# senseBox-MCU_v15.net
KiCad netlist of a schematic drawn in EAGLE
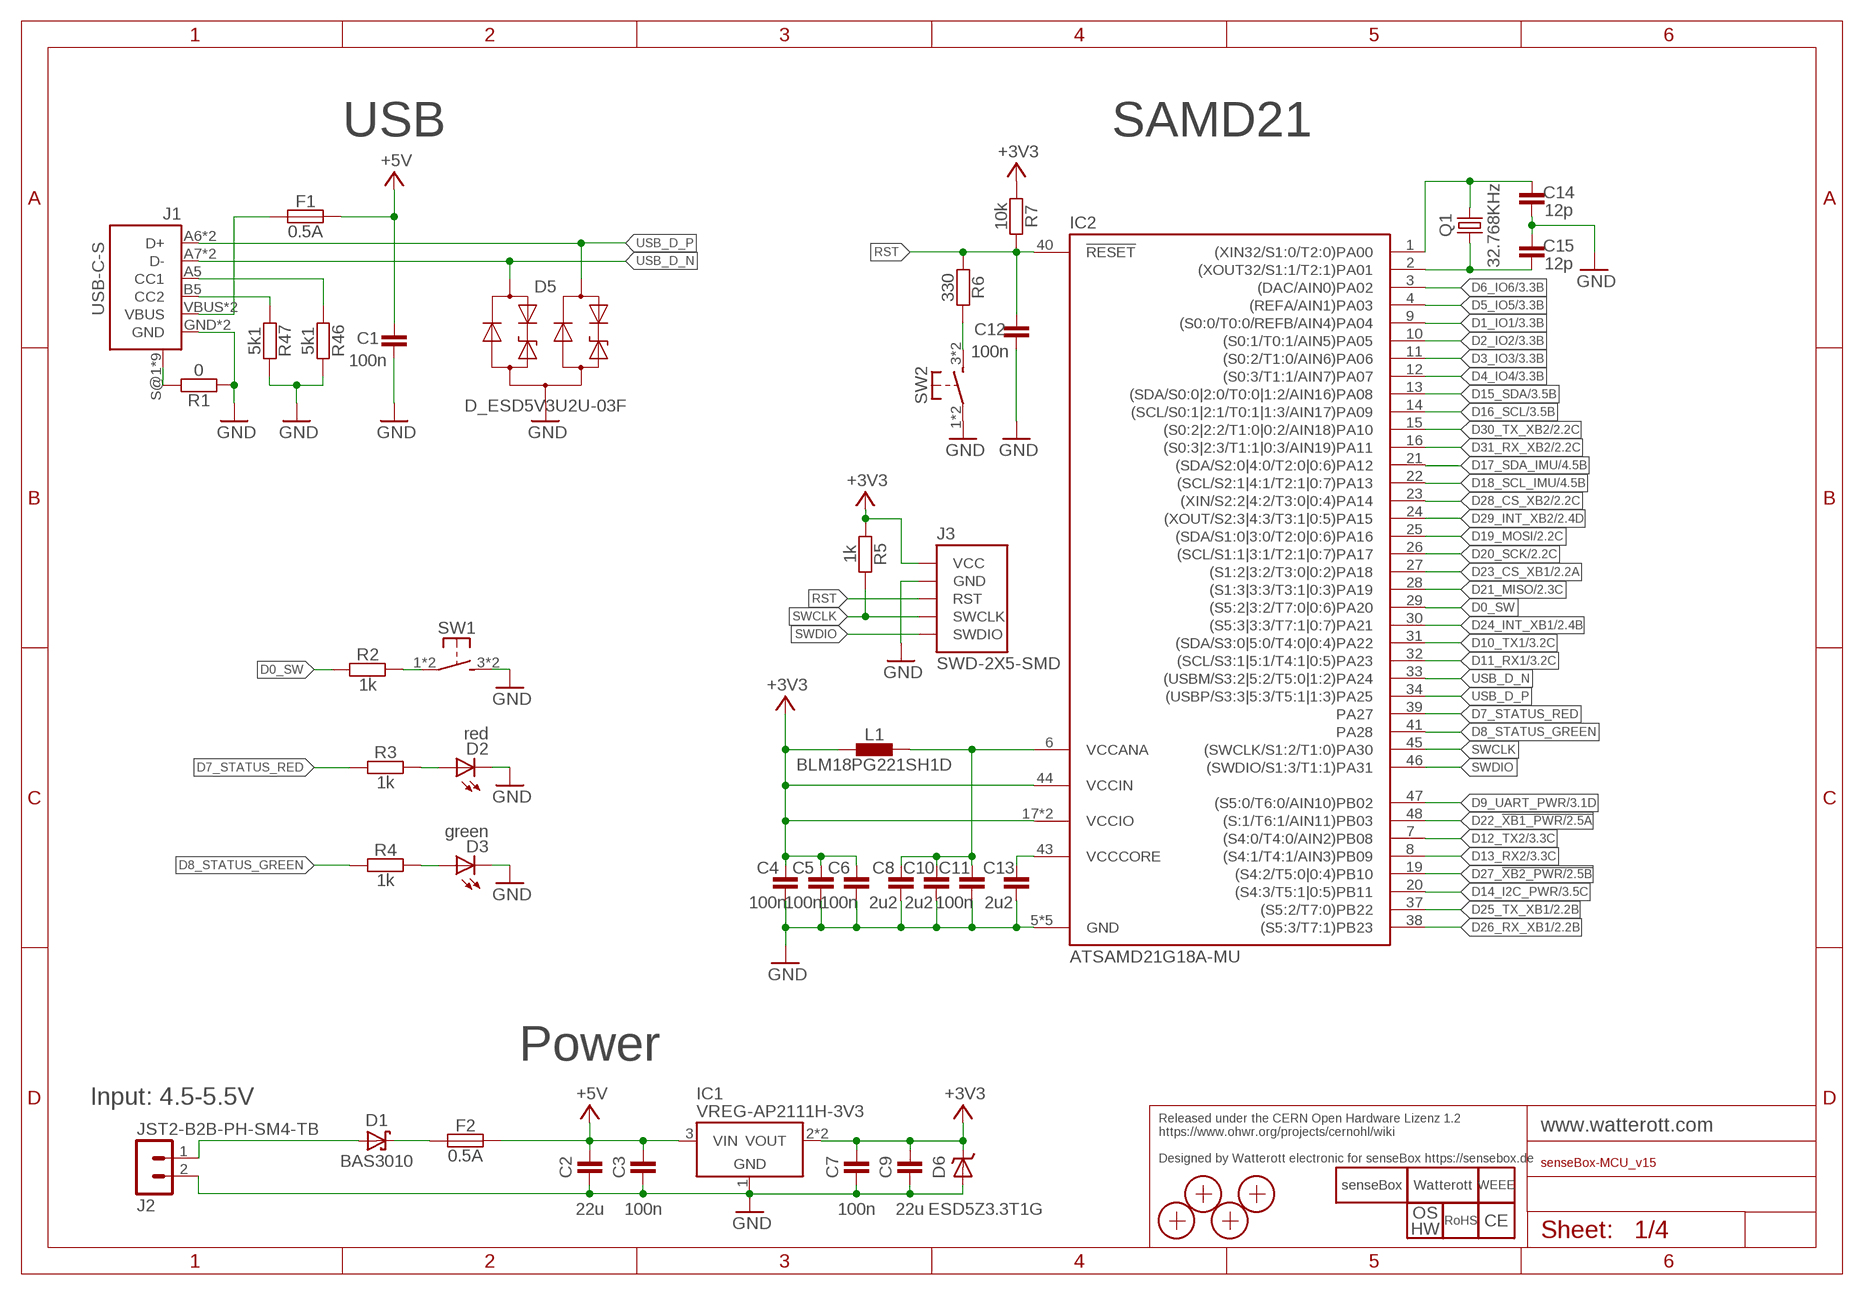
[diagram p0: schematic, sheet 1]
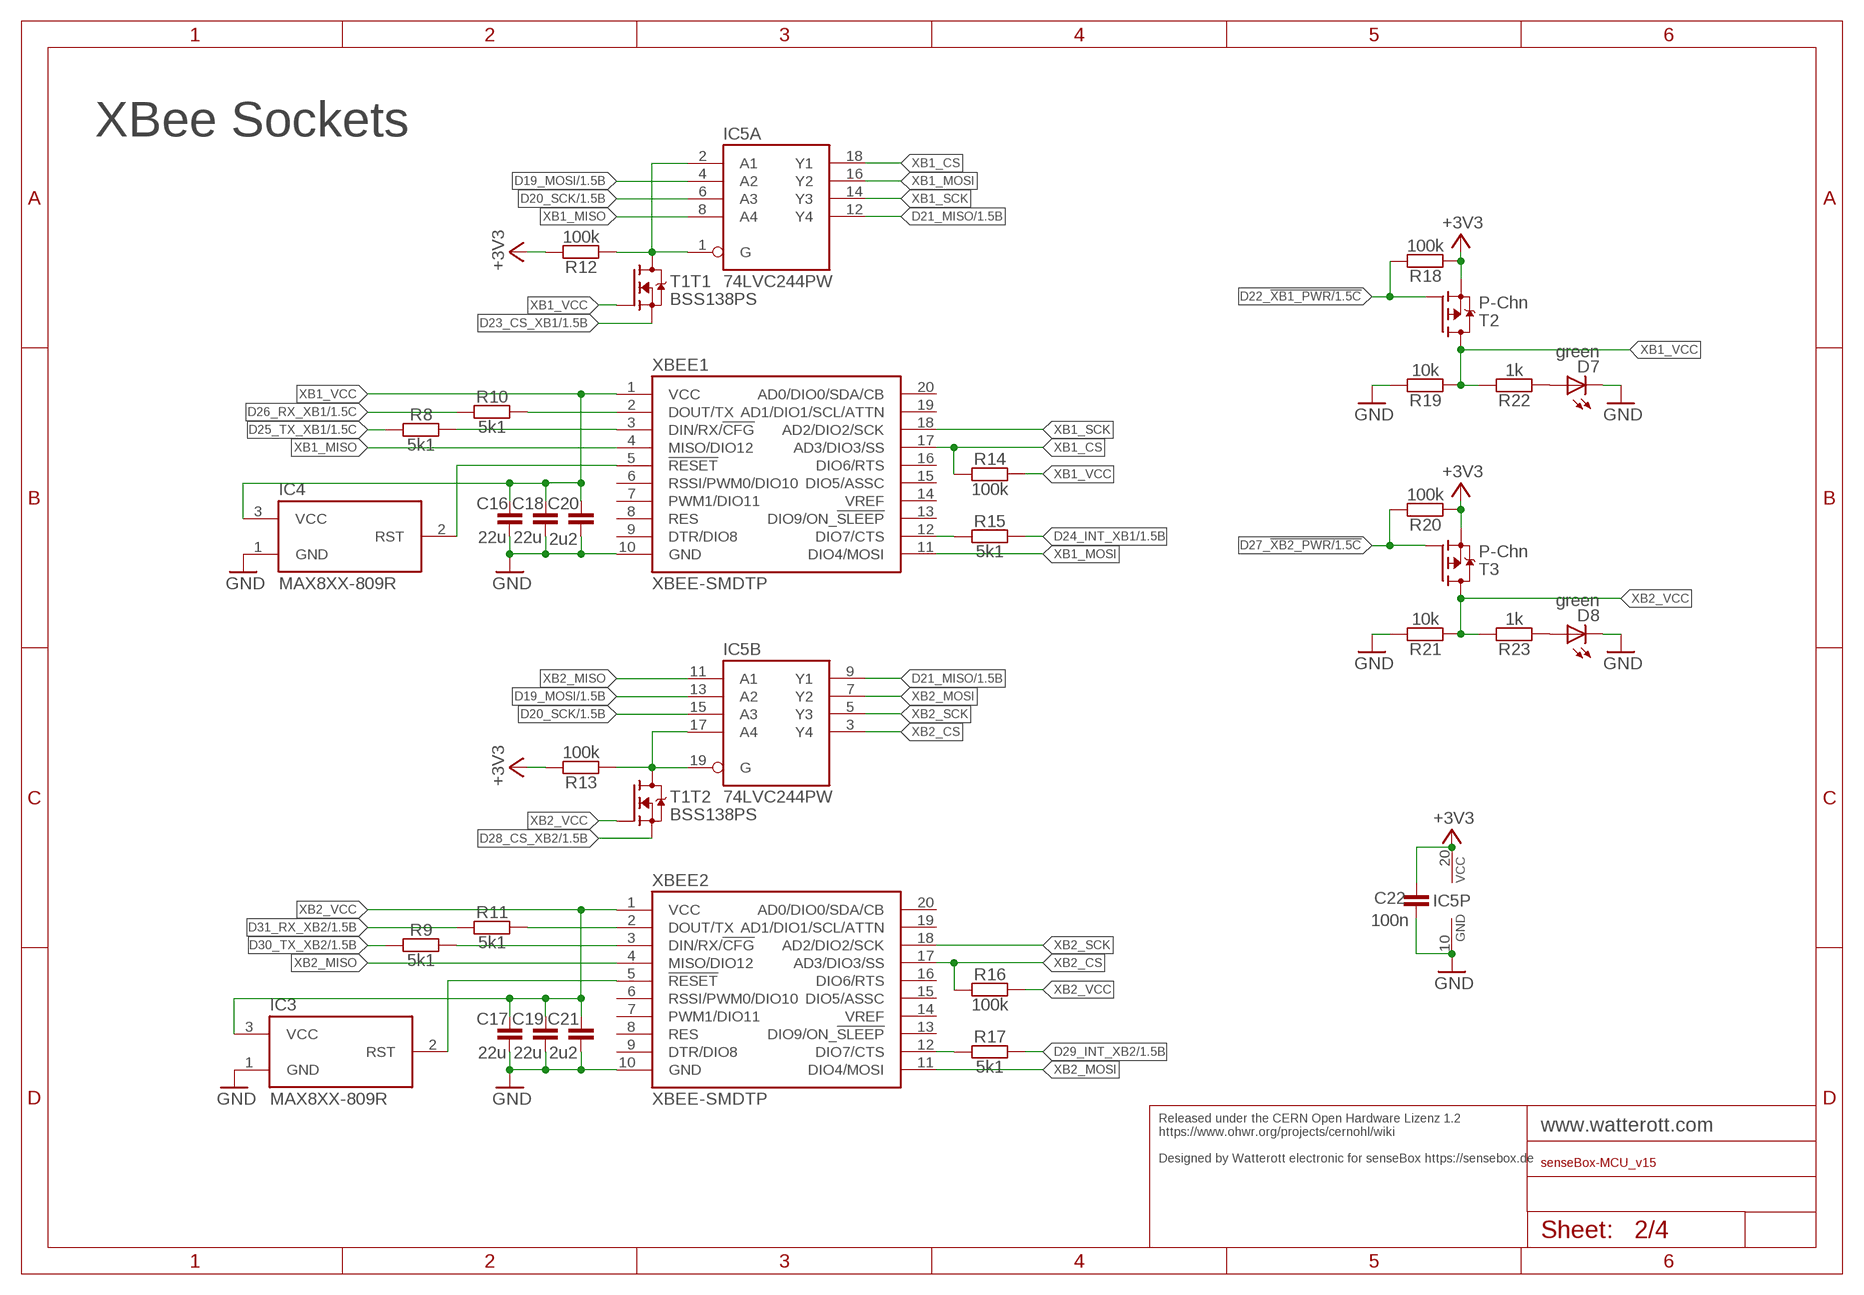
[diagram p1: schematic, sheet 2]
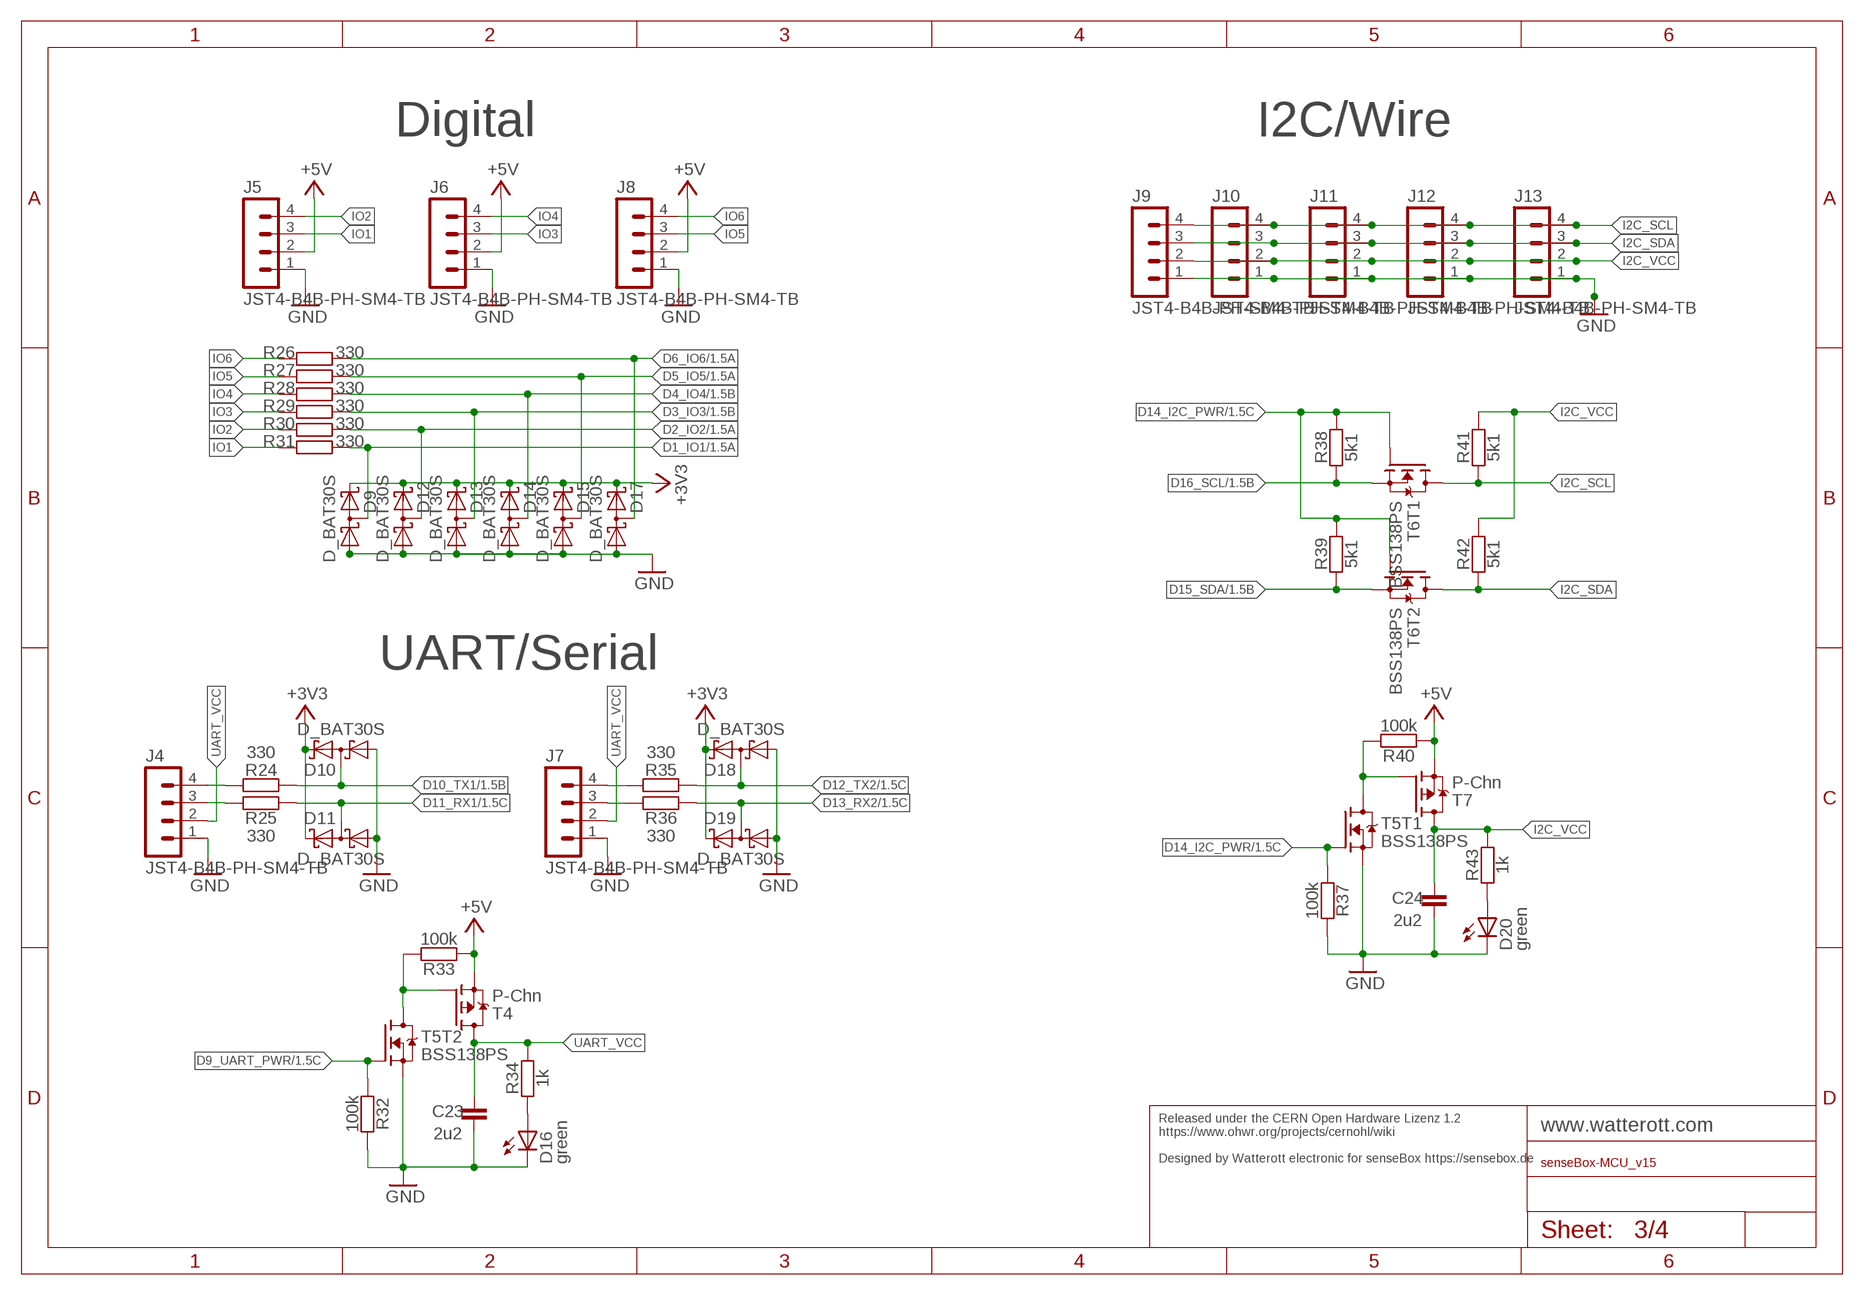
[diagram p2: schematic, sheet 3]
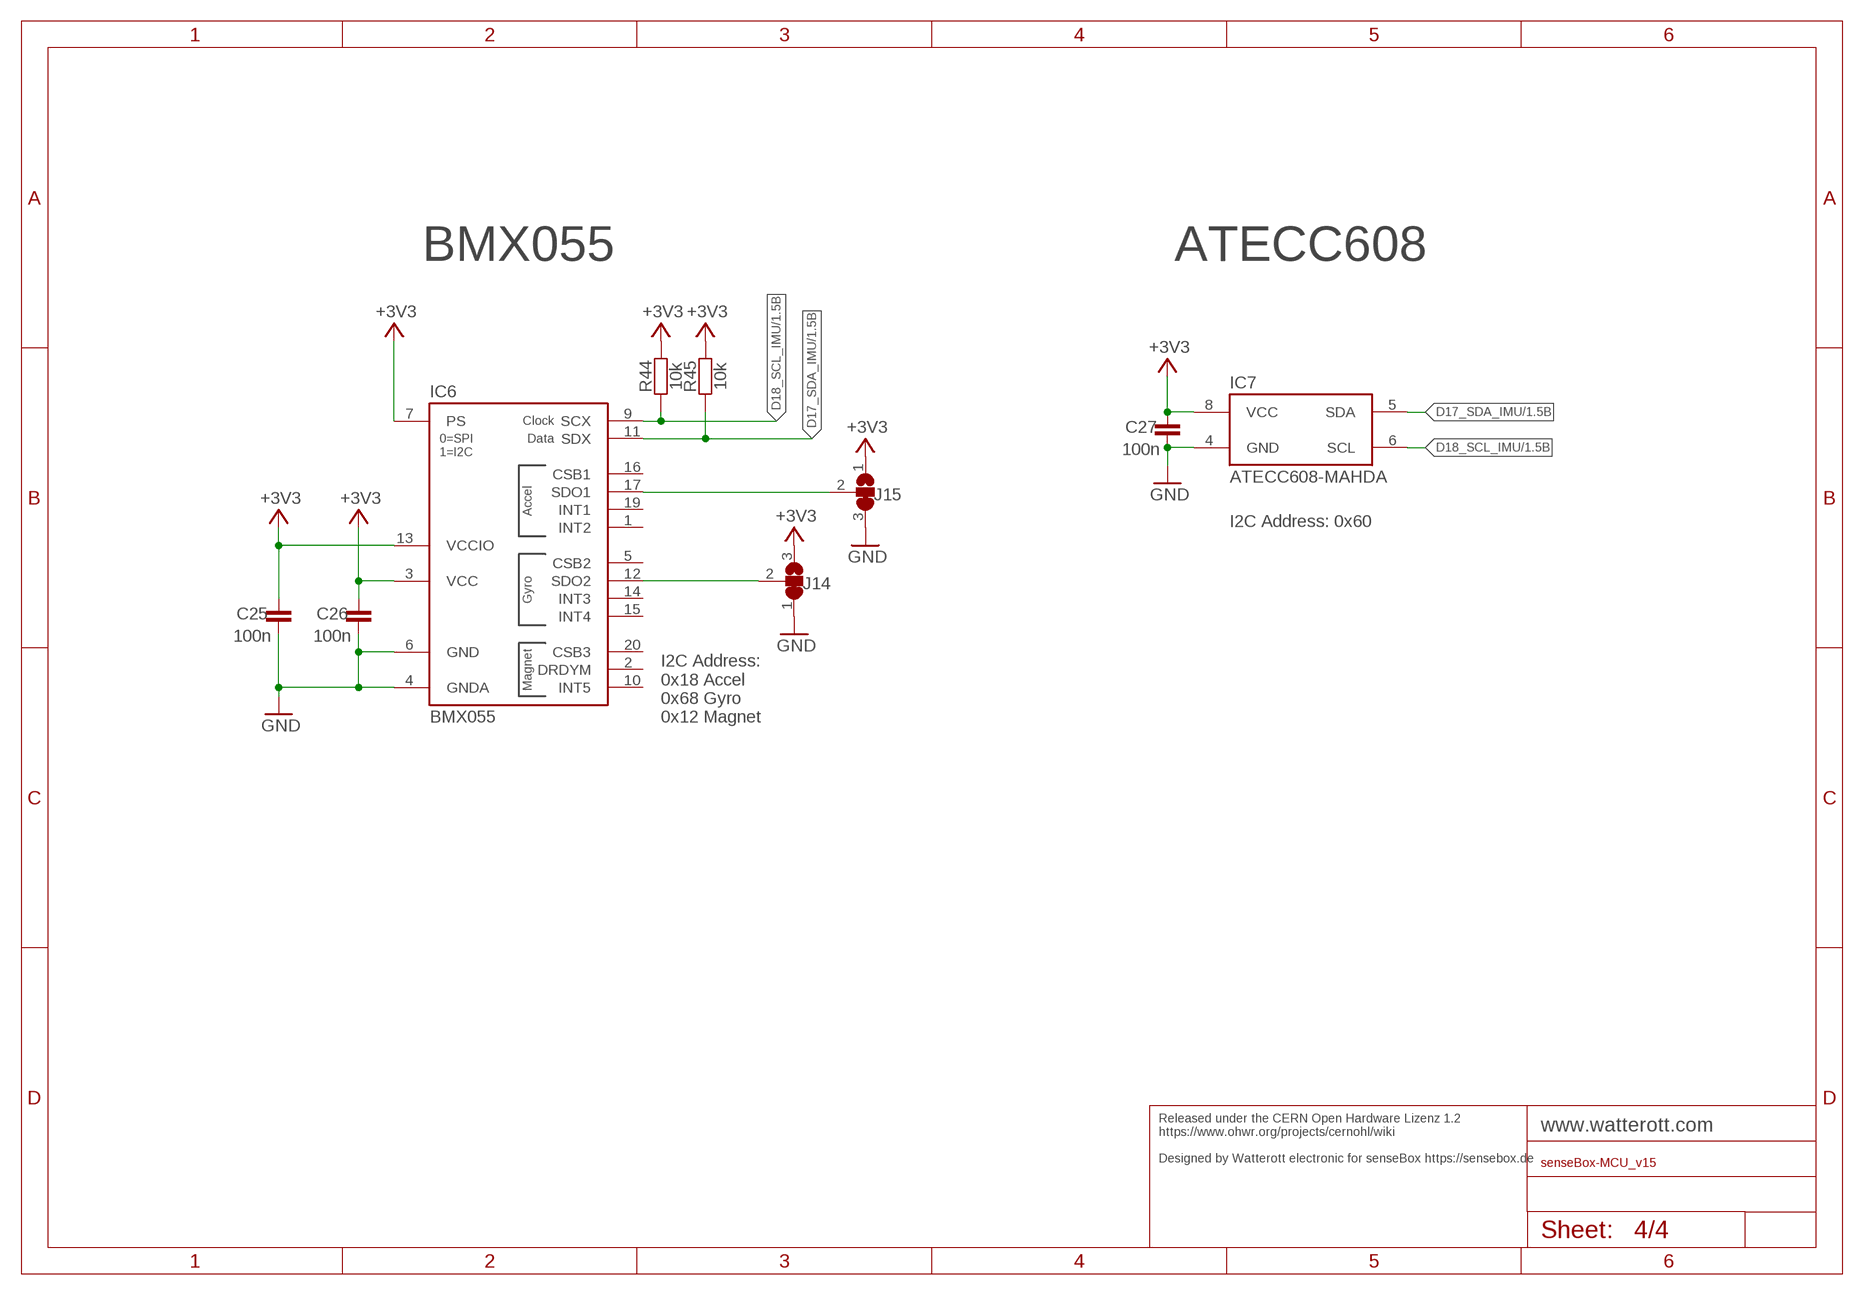
[diagram p3: schematic, sheet 4]

(export (version "E")
  (design (tool "Eeschema 10.0.6"))
  (components
    (comp (ref "C23")
      (value "2u2")
      (footprint "eagle-import:C0402")
      (libsource (lib "eagle-import") (part "CAPACITOR-0402"))
    )
    (comp (ref "C24")
      (value "2u2")
      (footprint "eagle-import:C0402")
      (libsource (lib "eagle-import") (part "CAPACITOR-0402"))
    )
    (comp (ref "D9")
      (value "D_BAT30S")
      (footprint "eagle-import:SOT323")
      (libsource (lib "eagle-import") (part "D_BAT30S"))
    )
    (comp (ref "D10")
      (value "D_BAT30S")
      (footprint "eagle-import:SOT323")
      (libsource (lib "eagle-import") (part "D_BAT30S"))
    )
    (comp (ref "D11")
      (value "D_BAT30S")
      (footprint "eagle-import:SOT323")
      (libsource (lib "eagle-import") (part "D_BAT30S"))
    )
    (comp (ref "D12")
      (value "D_BAT30S")
      (footprint "eagle-import:SOT323")
      (libsource (lib "eagle-import") (part "D_BAT30S"))
    )
    (comp (ref "D13")
      (value "D_BAT30S")
      (footprint "eagle-import:SOT323")
      (libsource (lib "eagle-import") (part "D_BAT30S"))
    )
    (comp (ref "D14")
      (value "D_BAT30S")
      (footprint "eagle-import:SOT323")
      (libsource (lib "eagle-import") (part "D_BAT30S"))
    )
    (comp (ref "D15")
      (value "D_BAT30S")
      (footprint "eagle-import:SOT323")
      (libsource (lib "eagle-import") (part "D_BAT30S"))
    )
    (comp (ref "D16")
      (value "green")
      (footprint "eagle-import:C0603")
      (libsource (lib "eagle-import") (part "LED-0603"))
    )
    (comp (ref "D17")
      (value "D_BAT30S")
      (footprint "eagle-import:SOT323")
      (libsource (lib "eagle-import") (part "D_BAT30S"))
    )
    (comp (ref "D18")
      (value "D_BAT30S")
      (footprint "eagle-import:SOT323")
      (libsource (lib "eagle-import") (part "D_BAT30S"))
    )
    (comp (ref "D19")
      (value "D_BAT30S")
      (footprint "eagle-import:SOT323")
      (libsource (lib "eagle-import") (part "D_BAT30S"))
    )
    (comp (ref "D20")
      (value "green")
      (footprint "eagle-import:C0603")
      (libsource (lib "eagle-import") (part "LED-0603"))
    )
    (comp (ref "J4")
      (value "JST4-B4B-PH-SM4-TB")
      (footprint "eagle-import:JST_B4B-PH-SM4-TB")
      (libsource (lib "eagle-import") (part "JST4-B4B-PH-SM4-TB"))
    )
    (comp (ref "J5")
      (value "JST4-B4B-PH-SM4-TB")
      (footprint "eagle-import:JST_B4B-PH-SM4-TB")
      (libsource (lib "eagle-import") (part "JST4-B4B-PH-SM4-TB"))
    )
    (comp (ref "J6")
      (value "JST4-B4B-PH-SM4-TB")
      (footprint "eagle-import:JST_B4B-PH-SM4-TB")
      (libsource (lib "eagle-import") (part "JST4-B4B-PH-SM4-TB"))
    )
    (comp (ref "J7")
      (value "JST4-B4B-PH-SM4-TB")
      (footprint "eagle-import:JST_B4B-PH-SM4-TB")
      (libsource (lib "eagle-import") (part "JST4-B4B-PH-SM4-TB"))
    )
    (comp (ref "J8")
      (value "JST4-B4B-PH-SM4-TB")
      (footprint "eagle-import:JST_B4B-PH-SM4-TB")
      (libsource (lib "eagle-import") (part "JST4-B4B-PH-SM4-TB"))
    )
    (comp (ref "J9")
      (value "JST4-B4B-PH-SM4-TB")
      (footprint "eagle-import:JST_B4B-PH-SM4-TB")
      (libsource (lib "eagle-import") (part "JST4-B4B-PH-SM4-TB"))
    )
    (comp (ref "J10")
      (value "JST4-B4B-PH-SM4-TB")
      (footprint "eagle-import:JST_B4B-PH-SM4-TB")
      (libsource (lib "eagle-import") (part "JST4-B4B-PH-SM4-TB"))
    )
    (comp (ref "J11")
      (value "JST4-B4B-PH-SM4-TB")
      (footprint "eagle-import:JST_B4B-PH-SM4-TB")
      (libsource (lib "eagle-import") (part "JST4-B4B-PH-SM4-TB"))
    )
    (comp (ref "J12")
      (value "JST4-B4B-PH-SM4-TB")
      (footprint "eagle-import:JST_B4B-PH-SM4-TB")
      (libsource (lib "eagle-import") (part "JST4-B4B-PH-SM4-TB"))
    )
    (comp (ref "J13")
      (value "JST4-B4B-PH-SM4-TB")
      (footprint "eagle-import:JST_B4B-PH-SM4-TB")
      (libsource (lib "eagle-import") (part "JST4-B4B-PH-SM4-TB"))
    )
    (comp (ref "R24")
      (value "330")
      (footprint "eagle-import:C0402")
      (libsource (lib "eagle-import") (part "RESISTOR-0402"))
    )
    (comp (ref "R25")
      (value "330")
      (footprint "eagle-import:C0402")
      (libsource (lib "eagle-import") (part "RESISTOR-0402"))
    )
    (comp (ref "R26")
      (value "330")
      (footprint "eagle-import:C0402")
      (libsource (lib "eagle-import") (part "RESISTOR-0402"))
    )
    (comp (ref "R27")
      (value "330")
      (footprint "eagle-import:C0402")
      (libsource (lib "eagle-import") (part "RESISTOR-0402"))
    )
    (comp (ref "R28")
      (value "330")
      (footprint "eagle-import:C0402")
      (libsource (lib "eagle-import") (part "RESISTOR-0402"))
    )
    (comp (ref "R29")
      (value "330")
      (footprint "eagle-import:C0402")
      (libsource (lib "eagle-import") (part "RESISTOR-0402"))
    )
    (comp (ref "R30")
      (value "330")
      (footprint "eagle-import:C0402")
      (libsource (lib "eagle-import") (part "RESISTOR-0402"))
    )
    (comp (ref "R31")
      (value "330")
      (footprint "eagle-import:C0402")
      (libsource (lib "eagle-import") (part "RESISTOR-0402"))
    )
    (comp (ref "R32")
      (value "100k")
      (footprint "eagle-import:C0402")
      (libsource (lib "eagle-import") (part "RESISTOR-0402"))
    )
    (comp (ref "R33")
      (value "100k")
      (footprint "eagle-import:C0402")
      (libsource (lib "eagle-import") (part "RESISTOR-0402"))
    )
    (comp (ref "R34")
      (value "1k")
      (footprint "eagle-import:C0402")
      (libsource (lib "eagle-import") (part "RESISTOR-0402"))
    )
    (comp (ref "R35")
      (value "330")
      (footprint "eagle-import:C0402")
      (libsource (lib "eagle-import") (part "RESISTOR-0402"))
    )
    (comp (ref "R36")
      (value "330")
      (footprint "eagle-import:C0402")
      (libsource (lib "eagle-import") (part "RESISTOR-0402"))
    )
    (comp (ref "R37")
      (value "100k")
      (footprint "eagle-import:C0402")
      (libsource (lib "eagle-import") (part "RESISTOR-0402"))
    )
    (comp (ref "R38")
      (value "5k1")
      (footprint "eagle-import:C0402")
      (libsource (lib "eagle-import") (part "RESISTOR-0402"))
    )
    (comp (ref "R39")
      (value "5k1")
      (footprint "eagle-import:C0402")
      (libsource (lib "eagle-import") (part "RESISTOR-0402"))
    )
    (comp (ref "R40")
      (value "100k")
      (footprint "eagle-import:C0402")
      (libsource (lib "eagle-import") (part "RESISTOR-0402"))
    )
    (comp (ref "R41")
      (value "5k1")
      (footprint "eagle-import:C0402")
      (libsource (lib "eagle-import") (part "RESISTOR-0402"))
    )
    (comp (ref "R42")
      (value "5k1")
      (footprint "eagle-import:C0402")
      (libsource (lib "eagle-import") (part "RESISTOR-0402"))
    )
    (comp (ref "R43")
      (value "1k")
      (footprint "eagle-import:C0402")
      (libsource (lib "eagle-import") (part "RESISTOR-0402"))
    )
    (comp (ref "T4")
      (value "P-Chn")
      (footprint "eagle-import:SOT23")
      (libsource (lib "eagle-import") (part "MOSFET-P-SOT23"))
    )
    (comp (ref "T5")
      (value "BSS138PS")
      (footprint "eagle-import:SOT363")
      (libsource (lib "eagle-import") (part "BSS138PS"))
    )
    (comp (ref "T6")
      (value "BSS138PS")
      (footprint "eagle-import:SOT363")
      (libsource (lib "eagle-import") (part "BSS138PS"))
    )
    (comp (ref "T7")
      (value "P-Chn")
      (footprint "eagle-import:SOT23")
      (libsource (lib "eagle-import") (part "MOSFET-P-SOT23"))
    )
    (comp (ref "C16")
      (value "22u")
      (footprint "eagle-import:C0805")
      (libsource (lib "eagle-import") (part "CAPACITOR-0805"))
    )
    (comp (ref "C17")
      (value "22u")
      (footprint "eagle-import:C0805")
      (libsource (lib "eagle-import") (part "CAPACITOR-0805"))
    )
    (comp (ref "C18")
      (value "22u")
      (footprint "eagle-import:C0805")
      (libsource (lib "eagle-import") (part "CAPACITOR-0805"))
    )
    (comp (ref "C19")
      (value "22u")
      (footprint "eagle-import:C0805")
      (libsource (lib "eagle-import") (part "CAPACITOR-0805"))
    )
    (comp (ref "C20")
      (value "2u2")
      (footprint "eagle-import:C0402")
      (libsource (lib "eagle-import") (part "CAPACITOR-0402"))
    )
    (comp (ref "C21")
      (value "2u2")
      (footprint "eagle-import:C0402")
      (libsource (lib "eagle-import") (part "CAPACITOR-0402"))
    )
    (comp (ref "C22")
      (value "100n")
      (footprint "eagle-import:C0402")
      (libsource (lib "eagle-import") (part "CAPACITOR-0402"))
    )
    (comp (ref "D7")
      (value "green")
      (footprint "eagle-import:C0603")
      (libsource (lib "eagle-import") (part "LED-0603"))
    )
    (comp (ref "D8")
      (value "green")
      (footprint "eagle-import:C0603")
      (libsource (lib "eagle-import") (part "LED-0603"))
    )
    (comp (ref "IC3")
      (value "MAX8XX-809R")
      (footprint "eagle-import:SOT23")
      (libsource (lib "eagle-import") (part "MAX8XX-809R"))
    )
    (comp (ref "IC4")
      (value "MAX8XX-809R")
      (footprint "eagle-import:SOT23")
      (libsource (lib "eagle-import") (part "MAX8XX-809R"))
    )
    (comp (ref "IC5")
      (value "74LVC244PW")
      (footprint "eagle-import:TSSOP20")
      (libsource (lib "eagle-import") (part "74244PWLVC"))
    )
    (comp (ref "R8")
      (value "5k1")
      (footprint "eagle-import:C0402")
      (libsource (lib "eagle-import") (part "RESISTOR-0402"))
    )
    (comp (ref "R9")
      (value "5k1")
      (footprint "eagle-import:C0402")
      (libsource (lib "eagle-import") (part "RESISTOR-0402"))
    )
    (comp (ref "R10")
      (value "5k1")
      (footprint "eagle-import:C0402")
      (libsource (lib "eagle-import") (part "RESISTOR-0402"))
    )
    (comp (ref "R11")
      (value "5k1")
      (footprint "eagle-import:C0402")
      (libsource (lib "eagle-import") (part "RESISTOR-0402"))
    )
    (comp (ref "R12")
      (value "100k")
      (footprint "eagle-import:C0402")
      (libsource (lib "eagle-import") (part "RESISTOR-0402"))
    )
    (comp (ref "R13")
      (value "100k")
      (footprint "eagle-import:C0402")
      (libsource (lib "eagle-import") (part "RESISTOR-0402"))
    )
    (comp (ref "R14")
      (value "100k")
      (footprint "eagle-import:C0402")
      (libsource (lib "eagle-import") (part "RESISTOR-0402"))
    )
    (comp (ref "R15")
      (value "5k1")
      (footprint "eagle-import:C0402")
      (libsource (lib "eagle-import") (part "RESISTOR-0402"))
    )
    (comp (ref "R16")
      (value "100k")
      (footprint "eagle-import:C0402")
      (libsource (lib "eagle-import") (part "RESISTOR-0402"))
    )
    (comp (ref "R17")
      (value "5k1")
      (footprint "eagle-import:C0402")
      (libsource (lib "eagle-import") (part "RESISTOR-0402"))
    )
    (comp (ref "R18")
      (value "100k")
      (footprint "eagle-import:C0402")
      (libsource (lib "eagle-import") (part "RESISTOR-0402"))
    )
    (comp (ref "R19")
      (value "10k")
      (footprint "eagle-import:C0402")
      (libsource (lib "eagle-import") (part "RESISTOR-0402"))
    )
    (comp (ref "R20")
      (value "100k")
      (footprint "eagle-import:C0402")
      (libsource (lib "eagle-import") (part "RESISTOR-0402"))
    )
    (comp (ref "R21")
      (value "10k")
      (footprint "eagle-import:C0402")
      (libsource (lib "eagle-import") (part "RESISTOR-0402"))
    )
    (comp (ref "R22")
      (value "1k")
      (footprint "eagle-import:C0402")
      (libsource (lib "eagle-import") (part "RESISTOR-0402"))
    )
    (comp (ref "R23")
      (value "1k")
      (footprint "eagle-import:C0402")
      (libsource (lib "eagle-import") (part "RESISTOR-0402"))
    )
    (comp (ref "T1")
      (value "BSS138PS")
      (footprint "eagle-import:SOT363")
      (libsource (lib "eagle-import") (part "BSS138PS"))
    )
    (comp (ref "T2")
      (value "P-Chn")
      (footprint "eagle-import:SOT23")
      (libsource (lib "eagle-import") (part "MOSFET-P-SOT23"))
    )
    (comp (ref "T3")
      (value "P-Chn")
      (footprint "eagle-import:SOT23")
      (libsource (lib "eagle-import") (part "MOSFET-P-SOT23"))
    )
    (comp (ref "XBEE1")
      (value "XBEE-SMDTP")
      (footprint "eagle-import:XBEE_SMD_TP")
      (libsource (lib "eagle-import") (part "XBEE-SMDTP"))
    )
    (comp (ref "XBEE2")
      (value "XBEE-SMDTP")
      (footprint "eagle-import:XBEE_SMD_TP")
      (libsource (lib "eagle-import") (part "XBEE-SMDTP"))
    )
    (comp (ref "C1")
      (value "100n")
      (footprint "eagle-import:C0402")
      (libsource (lib "eagle-import") (part "CAPACITOR-0402"))
    )
    (comp (ref "C2")
      (value "22u")
      (footprint "eagle-import:C0805")
      (libsource (lib "eagle-import") (part "CAPACITOR-0805"))
    )
    (comp (ref "C3")
      (value "100n")
      (footprint "eagle-import:C0402")
      (libsource (lib "eagle-import") (part "CAPACITOR-0402"))
    )
    (comp (ref "C4")
      (value "100n")
      (footprint "eagle-import:C0402")
      (libsource (lib "eagle-import") (part "CAPACITOR-0402"))
    )
    (comp (ref "C5")
      (value "100n")
      (footprint "eagle-import:C0402")
      (libsource (lib "eagle-import") (part "CAPACITOR-0402"))
    )
    (comp (ref "C6")
      (value "100n")
      (footprint "eagle-import:C0402")
      (libsource (lib "eagle-import") (part "CAPACITOR-0402"))
    )
    (comp (ref "C7")
      (value "100n")
      (footprint "eagle-import:C0402")
      (libsource (lib "eagle-import") (part "CAPACITOR-0402"))
    )
    (comp (ref "C8")
      (value "2u2")
      (footprint "eagle-import:C0402")
      (libsource (lib "eagle-import") (part "CAPACITOR-0402"))
    )
    (comp (ref "C9")
      (value "22u")
      (footprint "eagle-import:C0805")
      (libsource (lib "eagle-import") (part "CAPACITOR-0805"))
    )
    (comp (ref "C10")
      (value "2u2")
      (footprint "eagle-import:C0402")
      (libsource (lib "eagle-import") (part "CAPACITOR-0402"))
    )
    (comp (ref "C11")
      (value "100n")
      (footprint "eagle-import:C0402")
      (libsource (lib "eagle-import") (part "CAPACITOR-0402"))
    )
    (comp (ref "C12")
      (value "100n")
      (footprint "eagle-import:C0402")
      (libsource (lib "eagle-import") (part "CAPACITOR-0402"))
    )
    (comp (ref "C13")
      (value "2u2")
      (footprint "eagle-import:C0402")
      (libsource (lib "eagle-import") (part "CAPACITOR-0402"))
    )
    (comp (ref "C14")
      (value "12p")
      (footprint "eagle-import:C0402")
      (libsource (lib "eagle-import") (part "CAPACITOR-0402"))
    )
    (comp (ref "C15")
      (value "12p")
      (footprint "eagle-import:C0402")
      (libsource (lib "eagle-import") (part "CAPACITOR-0402"))
    )
    (comp (ref "D1")
      (value "BAS3010")
      (footprint "eagle-import:SOD323")
      (libsource (lib "eagle-import") (part "D_SCHOTTKY-SOD323"))
    )
    (comp (ref "D2")
      (value "red")
      (footprint "eagle-import:C0603")
      (libsource (lib "eagle-import") (part "LED-0603"))
    )
    (comp (ref "D3")
      (value "green")
      (footprint "eagle-import:C0603")
      (libsource (lib "eagle-import") (part "LED-0603"))
    )
    (comp (ref "D5")
      (value "D_ESD5V3U2U-03F")
      (footprint "eagle-import:SOT723")
      (libsource (lib "eagle-import") (part "D_ESD5V3U2U-03F"))
    )
    (comp (ref "D6")
      (value "ESD5Z3.3T1G")
      (footprint "eagle-import:SOD523")
      (libsource (lib "eagle-import") (part "D_TVS-SOD523"))
    )
    (comp (ref "F1")
      (value "0.5A")
      (footprint "eagle-import:C0805")
      (libsource (lib "eagle-import") (part "FUSE-0805"))
    )
    (comp (ref "F2")
      (value "0.5A")
      (footprint "eagle-import:C0805")
      (libsource (lib "eagle-import") (part "FUSE-0805"))
    )
    (comp (ref "IC1")
      (value "VREG-AP2111H-3V3")
      (footprint "eagle-import:SOT223")
      (libsource (lib "eagle-import") (part "VREG-TS1117CW-3V3"))
    )
    (comp (ref "IC2")
      (value "ATSAMD21G18A-MU")
      (footprint "eagle-import:QFN48-PAD")
      (libsource (lib "eagle-import") (part "ATSAMD21G18A-MU"))
    )
    (comp (ref "J1")
      (value "USB-C-S")
      (footprint "eagle-import:USB-C-S")
      (libsource (lib "eagle-import") (part "USB-C-S"))
    )
    (comp (ref "J2")
      (value "JST2-B2B-PH-SM4-TB")
      (footprint "eagle-import:JST_B2B-PH-SM4-TB")
      (libsource (lib "eagle-import") (part "JST2-B2B-PH-SM4-TB"))
    )
    (comp (ref "J3")
      (value "SWD-2X5-SMD")
      (footprint "eagle-import:SWD-2X5_SMD")
      (libsource (lib "eagle-import") (part "SWD-2X5-SMD"))
    )
    (comp (ref "L1")
      (value "BLM18PG221SH1D")
      (footprint "eagle-import:C0603")
      (libsource (lib "eagle-import") (part "INDUCTOR-0603"))
    )
    (comp (ref "LOGO1")
      (value "LOGO_SENSEBOX-12")
      (footprint "eagle-import:SB_12MM")
      (libsource (lib "eagle-import") (part "LOGO_SENSEBOX-12"))
    )
    (comp (ref "LOGO3")
      (value "OSHW_LOGOX0070")
      (footprint "eagle-import:OSHW_3MM")
      (libsource (lib "eagle-import") (part "LOGO_OSHW-3"))
    )
    (comp (ref "LOGO4")
      (value "LOGO_SPARK-4")
      (footprint "eagle-import:SPARK_4MM")
      (libsource (lib "eagle-import") (part "LOGO_SPARK-4"))
    )
    (comp (ref "LOGO5")
      (value "LOGO_ROHS-4")
      (footprint "eagle-import:ROHS_4MM")
      (libsource (lib "eagle-import") (part "LOGO_ROHS-4"))
    )
    (comp (ref "LOGO6")
      (value "LOGO_WEEE-4")
      (footprint "eagle-import:WEEE_4MM")
      (libsource (lib "eagle-import") (part "LOGO_WEEE-4"))
    )
    (comp (ref "LOGO7")
      (value "LOGO_CE-4")
      (footprint "eagle-import:CE_4MM")
      (libsource (lib "eagle-import") (part "LOGO_CE-4"))
    )
    (comp (ref "Q1")
      (value "32.768KHz")
      (footprint "eagle-import:CRYSTAL_ZM315")
      (libsource (lib "eagle-import") (part "CRYSTAL-ZM315"))
    )
    (comp (ref "R1")
      (value "0")
      (footprint "eagle-import:C0402")
      (libsource (lib "eagle-import") (part "RESISTOR-0402"))
    )
    (comp (ref "R2")
      (value "1k")
      (footprint "eagle-import:C0402")
      (libsource (lib "eagle-import") (part "RESISTOR-0402"))
    )
    (comp (ref "R3")
      (value "1k")
      (footprint "eagle-import:C0402")
      (libsource (lib "eagle-import") (part "RESISTOR-0402"))
    )
    (comp (ref "R4")
      (value "1k")
      (footprint "eagle-import:C0402")
      (libsource (lib "eagle-import") (part "RESISTOR-0402"))
    )
    (comp (ref "R5")
      (value "1k")
      (footprint "eagle-import:C0402")
      (libsource (lib "eagle-import") (part "RESISTOR-0402"))
    )
    (comp (ref "R6")
      (value "330")
      (footprint "eagle-import:C0402")
      (libsource (lib "eagle-import") (part "RESISTOR-0402"))
    )
    (comp (ref "R7")
      (value "10k")
      (footprint "eagle-import:C0402")
      (libsource (lib "eagle-import") (part "RESISTOR-0402"))
    )
    (comp (ref "R46")
      (value "5k1")
      (footprint "eagle-import:C0402")
      (libsource (lib "eagle-import") (part "RESISTOR-0402"))
    )
    (comp (ref "R47")
      (value "5k1")
      (footprint "eagle-import:C0402")
      (libsource (lib "eagle-import") (part "RESISTOR-0402"))
    )
    (comp (ref "SW1")
      (value "PTS645SH50SMTR92-Grey")
      (footprint "eagle-import:SW6X6_SMD")
      (libsource (lib "eagle-import") (part "SW-TACTILE-6X6_SMD"))
    )
    (comp (ref "SW2")
      (value "PTS645SK50SMTR92-Red")
      (footprint "eagle-import:SW6X6_SMD")
      (libsource (lib "eagle-import") (part "SW-TACTILE-6X6_SMD"))
    )
    (comp (ref "X1")
      (value "PASSER-07")
      (footprint "eagle-import:PASSER_07MM")
      (libsource (lib "eagle-import") (part "PASSER-07"))
    )
    (comp (ref "X2")
      (value "PASSER-07")
      (footprint "eagle-import:PASSER_07MM")
      (libsource (lib "eagle-import") (part "PASSER-07"))
    )
    (comp (ref "X3")
      (value "PASSER-07")
      (footprint "eagle-import:PASSER_07MM")
      (libsource (lib "eagle-import") (part "PASSER-07"))
    )
    (comp (ref "X4")
      (value "PASSER-07")
      (footprint "eagle-import:PASSER_07MM")
      (libsource (lib "eagle-import") (part "PASSER-07"))
    )
    (comp (ref "C25")
      (value "100n")
      (footprint "eagle-import:C0402")
      (libsource (lib "eagle-import") (part "CAPACITOR-0402"))
    )
    (comp (ref "C26")
      (value "100n")
      (footprint "eagle-import:C0402")
      (libsource (lib "eagle-import") (part "CAPACITOR-0402"))
    )
    (comp (ref "C27")
      (value "100n")
      (footprint "eagle-import:C0402")
      (libsource (lib "eagle-import") (part "CAPACITOR-0402"))
    )
    (comp (ref "IC6")
      (value "BMX055")
      (footprint "eagle-import:BMX055")
      (libsource (lib "eagle-import") (part "BMX055"))
    )
    (comp (ref "IC7")
      (value "ATECC608-MAHDA")
      (footprint "eagle-import:UDFN8")
      (libsource (lib "eagle-import") (part "ATECC608A-MAHDA"))
    )
    (comp (ref "J14")
      (value "JUMPER3-0402")
      (footprint "eagle-import:JUMPER3-0402")
      (libsource (lib "eagle-import") (part "JUMPER3-0402"))
    )
    (comp (ref "J15")
      (value "JUMPER3-0402")
      (footprint "eagle-import:JUMPER3-0402")
      (libsource (lib "eagle-import") (part "JUMPER3-0402"))
    )
    (comp (ref "R44")
      (value "10k")
      (footprint "eagle-import:C0402")
      (libsource (lib "eagle-import") (part "RESISTOR-0402"))
    )
    (comp (ref "R45")
      (value "10k")
      (footprint "eagle-import:C0402")
      (libsource (lib "eagle-import") (part "RESISTOR-0402"))
    )
  )
  (nets
    (net (code "1") (name "+3V3") (class "Default")
      (node (ref "C22") (pin "2") (pinfunction "2_2") (pintype "passive"))
      (node (ref "C25") (pin "2") (pinfunction "2_2") (pintype "passive"))
      (node (ref "C26") (pin "2") (pinfunction "2_2") (pintype "passive"))
      (node (ref "C27") (pin "2") (pinfunction "2_2") (pintype "passive"))
      (node (ref "C4") (pin "2") (pinfunction "2_2") (pintype "passive"))
      (node (ref "C5") (pin "2") (pinfunction "2_2") (pintype "passive"))
      (node (ref "C6") (pin "2") (pinfunction "2_2") (pintype "passive"))
      (node (ref "C7") (pin "2") (pinfunction "2_2") (pintype "passive"))
      (node (ref "C9") (pin "2") (pinfunction "2_2") (pintype "passive"))
      (node (ref "D10") (pin "2") (pinfunction "C_2") (pintype "passive"))
      (node (ref "D11") (pin "2") (pinfunction "C_2") (pintype "passive"))
      (node (ref "D12") (pin "2") (pinfunction "C_2") (pintype "passive"))
      (node (ref "D13") (pin "2") (pinfunction "C_2") (pintype "passive"))
      (node (ref "D14") (pin "2") (pinfunction "C_2") (pintype "passive"))
      (node (ref "D15") (pin "2") (pinfunction "C_2") (pintype "passive"))
      (node (ref "D17") (pin "2") (pinfunction "C_2") (pintype "passive"))
      (node (ref "D18") (pin "2") (pinfunction "C_2") (pintype "passive"))
      (node (ref "D19") (pin "2") (pinfunction "C_2") (pintype "passive"))
      (node (ref "D6") (pin "C") (pinfunction "C_C") (pintype "passive"))
      (node (ref "D9") (pin "2") (pinfunction "C_2") (pintype "passive"))
      (node (ref "IC1") (pin "2") (pinfunction "VOUT_2") (pintype "power_in"))
      (node (ref "IC1") (pin "4") (pinfunction "VOUT_4") (pintype "power_in"))
      (node (ref "IC2") (pin "17") (pinfunction "VCCIO_17") (pintype "power_in"))
      (node (ref "IC2") (pin "36") (pinfunction "VCCIO_36") (pintype "power_in"))
      (node (ref "IC2") (pin "44") (pinfunction "VCCIN_44") (pintype "power_in"))
      (node (ref "IC5") (pin "20") (pinfunction "VCC_20") (pintype "power_in"))
      (node (ref "IC6") (pin "13") (pinfunction "VCCIO_13") (pintype "power_in"))
      (node (ref "IC6") (pin "3") (pinfunction "VCC_3") (pintype "power_in"))
      (node (ref "IC6") (pin "7") (pinfunction "PS_7") (pintype "input"))
      (node (ref "IC7") (pin "8") (pinfunction "VCC_8") (pintype "power_in"))
      (node (ref "J14") (pin "3") (pinfunction "3_3") (pintype "passive"))
      (node (ref "J15") (pin "1") (pinfunction "1_1") (pintype "passive"))
      (node (ref "J3") (pin "VCC") (pinfunction "VCC_VCC") (pintype "power_in"))
      (node (ref "L1") (pin "1") (pinfunction "1_1") (pintype "passive"))
      (node (ref "R12") (pin "2") (pinfunction "2_2") (pintype "passive"))
      (node (ref "R13") (pin "2") (pinfunction "2_2") (pintype "passive"))
      (node (ref "R18") (pin "1") (pinfunction "1_1") (pintype "passive"))
      (node (ref "R20") (pin "1") (pinfunction "1_1") (pintype "passive"))
      (node (ref "R44") (pin "2") (pinfunction "2_2") (pintype "passive"))
      (node (ref "R45") (pin "2") (pinfunction "2_2") (pintype "passive"))
      (node (ref "R5") (pin "1") (pinfunction "1_1") (pintype "passive"))
      (node (ref "R7") (pin "1") (pinfunction "1_1") (pintype "passive"))
      (node (ref "T2") (pin "2") (pinfunction "S_2") (pintype "passive"))
      (node (ref "T3") (pin "2") (pinfunction "S_2") (pintype "passive"))
    )
    (net (code "2") (name "+5V") (class "Default")
      (node (ref "C1") (pin "2") (pinfunction "2_2") (pintype "passive"))
      (node (ref "C2") (pin "2") (pinfunction "2_2") (pintype "passive"))
      (node (ref "C3") (pin "2") (pinfunction "2_2") (pintype "passive"))
      (node (ref "F1") (pin "2") (pinfunction "2_2") (pintype "passive"))
      (node (ref "F2") (pin "2") (pinfunction "2_2") (pintype "passive"))
      (node (ref "IC1") (pin "3") (pinfunction "VIN_3") (pintype "power_in"))
      (node (ref "J5") (pin "2") (pinfunction "2_2") (pintype "passive"))
      (node (ref "J6") (pin "2") (pinfunction "2_2") (pintype "passive"))
      (node (ref "J8") (pin "2") (pinfunction "2_2") (pintype "passive"))
      (node (ref "R33") (pin "1") (pinfunction "1_1") (pintype "passive"))
      (node (ref "R40") (pin "1") (pinfunction "1_1") (pintype "passive"))
      (node (ref "T4") (pin "2") (pinfunction "S_2") (pintype "passive"))
      (node (ref "T7") (pin "2") (pinfunction "S_2") (pintype "passive"))
    )
    (net (code "3") (name "D0_SW") (class "Default")
      (node (ref "IC2") (pin "29") (pinfunction "(S5:2|3:2/T7:0|0:6)PA20_29") (pintype "bidirectional"))
      (node (ref "R2") (pin "1") (pinfunction "1_1") (pintype "passive"))
    )
    (net (code "4") (name "D1_IO1") (class "Default")
      (node (ref "D9") (pin "3") (pinfunction "CA_3") (pintype "passive"))
      (node (ref "IC2") (pin "9") (pinfunction "(S0:0/T0:0/REFB/AIN4)PA04_9") (pintype "bidirectional"))
      (node (ref "R31") (pin "1") (pinfunction "1_1") (pintype "passive"))
    )
    (net (code "5") (name "D2_IO2") (class "Default")
      (node (ref "D12") (pin "3") (pinfunction "CA_3") (pintype "passive"))
      (node (ref "IC2") (pin "10") (pinfunction "(S0:1/T0:1/AIN5)PA05_10") (pintype "bidirectional"))
      (node (ref "R30") (pin "1") (pinfunction "1_1") (pintype "passive"))
    )
    (net (code "6") (name "D3_IO3") (class "Default")
      (node (ref "D13") (pin "3") (pinfunction "CA_3") (pintype "passive"))
      (node (ref "IC2") (pin "11") (pinfunction "(S0:2/T1:0/AIN6)PA06_11") (pintype "bidirectional"))
      (node (ref "R29") (pin "1") (pinfunction "1_1") (pintype "passive"))
    )
    (net (code "7") (name "D4_IO4") (class "Default")
      (node (ref "D14") (pin "3") (pinfunction "CA_3") (pintype "passive"))
      (node (ref "IC2") (pin "12") (pinfunction "(S0:3/T1:1/AIN7)PA07_12") (pintype "bidirectional"))
      (node (ref "R28") (pin "1") (pinfunction "1_1") (pintype "passive"))
    )
    (net (code "8") (name "D5_IO5") (class "Default")
      (node (ref "D15") (pin "3") (pinfunction "CA_3") (pintype "passive"))
      (node (ref "IC2") (pin "4") (pinfunction "(REFA/AIN1)PA03_4") (pintype "bidirectional"))
      (node (ref "R27") (pin "1") (pinfunction "1_1") (pintype "passive"))
    )
    (net (code "9") (name "D6_IO6") (class "Default")
      (node (ref "D17") (pin "3") (pinfunction "CA_3") (pintype "passive"))
      (node (ref "IC2") (pin "3") (pinfunction "(DAC/AIN0)PA02_3") (pintype "bidirectional"))
      (node (ref "R26") (pin "1") (pinfunction "1_1") (pintype "passive"))
    )
    (net (code "10") (name "D7_STATUS_RED") (class "Default")
      (node (ref "IC2") (pin "39") (pinfunction "PA27_39") (pintype "bidirectional"))
      (node (ref "R3") (pin "1") (pinfunction "1_1") (pintype "passive"))
    )
    (net (code "11") (name "D8_STATUS_GREEN") (class "Default")
      (node (ref "IC2") (pin "41") (pinfunction "PA28_41") (pintype "bidirectional"))
      (node (ref "R4") (pin "1") (pinfunction "1_1") (pintype "passive"))
    )
    (net (code "12") (name "D9_UART_PWR") (class "Default")
      (node (ref "IC2") (pin "47") (pinfunction "(S5:0/T6:0/AIN10)PB02_47") (pintype "bidirectional"))
      (node (ref "R32") (pin "1") (pinfunction "1_1") (pintype "passive"))
      (node (ref "T5") (pin "5") (pinfunction "G_5") (pintype "passive"))
    )
    (net (code "13") (name "D10_TX1") (class "Default")
      (node (ref "D10") (pin "3") (pinfunction "CA_3") (pintype "passive"))
      (node (ref "IC2") (pin "31") (pinfunction "(SDA/S3:0|5:0/T4:0|0:4)PA22_31") (pintype "bidirectional"))
      (node (ref "R24") (pin "1") (pinfunction "1_1") (pintype "passive"))
    )
    (net (code "14") (name "D11_RX1") (class "Default")
      (node (ref "D11") (pin "3") (pinfunction "CA_3") (pintype "passive"))
      (node (ref "IC2") (pin "32") (pinfunction "(SCL/S3:1|5:1/T4:1|0:5)PA23_32") (pintype "bidirectional"))
      (node (ref "R25") (pin "1") (pinfunction "1_1") (pintype "passive"))
    )
    (net (code "15") (name "D12_TX2") (class "Default")
      (node (ref "D18") (pin "3") (pinfunction "CA_3") (pintype "passive"))
      (node (ref "IC2") (pin "7") (pinfunction "(S4:0/T4:0/AIN2)PB08_7") (pintype "bidirectional"))
      (node (ref "R35") (pin "1") (pinfunction "1_1") (pintype "passive"))
    )
    (net (code "16") (name "D13_RX2") (class "Default")
      (node (ref "D19") (pin "3") (pinfunction "CA_3") (pintype "passive"))
      (node (ref "IC2") (pin "8") (pinfunction "(S4:1/T4:1/AIN3)PB09_8") (pintype "bidirectional"))
      (node (ref "R36") (pin "1") (pinfunction "1_1") (pintype "passive"))
    )
    (net (code "17") (name "D14_I2C_PWR") (class "Default")
      (node (ref "IC2") (pin "20") (pinfunction "(S4:3/T5:1|0:5)PB11_20") (pintype "bidirectional"))
      (node (ref "R37") (pin "1") (pinfunction "1_1") (pintype "passive"))
      (node (ref "R38") (pin "2") (pinfunction "2_2") (pintype "passive"))
      (node (ref "R39") (pin "2") (pinfunction "2_2") (pintype "passive"))
      (node (ref "T5") (pin "2") (pinfunction "G_2") (pintype "passive"))
      (node (ref "T6") (pin "2") (pinfunction "G_2") (pintype "passive"))
      (node (ref "T6") (pin "5") (pinfunction "G_5") (pintype "passive"))
    )
    (net (code "18") (name "D15_SDA") (class "Default")
      (node (ref "IC2") (pin "13") (pinfunction "(SDA/S0:0|2:0/T0:0|1:2/AIN16)PA08_13") (pintype "bidirectional"))
      (node (ref "R39") (pin "1") (pinfunction "1_1") (pintype "passive"))
      (node (ref "T6") (pin "4") (pinfunction "S_4") (pintype "passive"))
    )
    (net (code "19") (name "D16_SCL") (class "Default")
      (node (ref "IC2") (pin "14") (pinfunction "(SCL/S0:1|2:1/T0:1|1:3/AIN17)PA09_14") (pintype "bidirectional"))
      (node (ref "R38") (pin "1") (pinfunction "1_1") (pintype "passive"))
      (node (ref "T6") (pin "1") (pinfunction "S_1") (pintype "passive"))
    )
    (net (code "20") (name "D17_SDA_IMU") (class "Default")
      (node (ref "IC2") (pin "21") (pinfunction "(SDA/S2:0|4:0/T2:0|0:6)PA12_21") (pintype "bidirectional"))
      (node (ref "IC6") (pin "11") (pinfunction "SDX_11") (pintype "bidirectional"))
      (node (ref "IC7") (pin "5") (pinfunction "SDA_5") (pintype "bidirectional"))
      (node (ref "R45") (pin "1") (pinfunction "1_1") (pintype "passive"))
    )
    (net (code "21") (name "D18_SCL_IMU") (class "Default")
      (node (ref "IC2") (pin "22") (pinfunction "(SCL/S2:1|4:1/T2:1|0:7)PA13_22") (pintype "bidirectional"))
      (node (ref "IC6") (pin "9") (pinfunction "SCX_9") (pintype "bidirectional"))
      (node (ref "IC7") (pin "6") (pinfunction "SCL_6") (pintype "bidirectional"))
      (node (ref "R44") (pin "1") (pinfunction "1_1") (pintype "passive"))
    )
    (net (code "22") (name "D19_MOSI") (class "Default")
      (node (ref "IC2") (pin "25") (pinfunction "(SDA/S1:0|3:0/T2:0|0:6)PA16_25") (pintype "bidirectional"))
      (node (ref "IC5") (pin "13") (pinfunction "A2_13") (pintype "input"))
      (node (ref "IC5") (pin "4") (pinfunction "A2_4") (pintype "input"))
    )
    (net (code "23") (name "D20_SCK") (class "Default")
      (node (ref "IC2") (pin "26") (pinfunction "(SCL/S1:1|3:1/T2:1|0:7)PA17_26") (pintype "bidirectional"))
      (node (ref "IC5") (pin "15") (pinfunction "A3_15") (pintype "input"))
      (node (ref "IC5") (pin "6") (pinfunction "A3_6") (pintype "input"))
    )
    (net (code "24") (name "D21_MISO") (class "Default")
      (node (ref "IC2") (pin "28") (pinfunction "(S1:3|3:3/T3:1|0:3)PA19_28") (pintype "bidirectional"))
      (node (ref "IC5") (pin "12") (pinfunction "Y4_12") (pintype "tri_state"))
      (node (ref "IC5") (pin "9") (pinfunction "Y1_9") (pintype "tri_state"))
    )
    (net (code "25") (name "D22_~{XB1_PWR}") (class "Default")
      (node (ref "IC2") (pin "48") (pinfunction "(S:1/T6:1/AIN11)PB03_48") (pintype "bidirectional"))
      (node (ref "R18") (pin "2") (pinfunction "2_2") (pintype "passive"))
      (node (ref "T2") (pin "1") (pinfunction "G_1") (pintype "passive"))
    )
    (net (code "26") (name "D23_CS_XB1") (class "Default")
      (node (ref "IC2") (pin "27") (pinfunction "(S1:2|3:2/T3:0|0:2)PA18_27") (pintype "bidirectional"))
      (node (ref "T1") (pin "1") (pinfunction "S_1") (pintype "passive"))
    )
    (net (code "27") (name "D24_INT_XB1") (class "Default")
      (node (ref "IC2") (pin "30") (pinfunction "(S5:3|3:3/T7:1|0:7)PA21_30") (pintype "bidirectional"))
      (node (ref "R15") (pin "2") (pinfunction "2_2") (pintype "passive"))
    )
    (net (code "28") (name "D25_TX_XB1") (class "Default")
      (node (ref "IC2") (pin "37") (pinfunction "(S5:2/T7:0)PB22_37") (pintype "bidirectional"))
      (node (ref "R8") (pin "1") (pinfunction "1_1") (pintype "passive"))
    )
    (net (code "29") (name "D26_RX_XB1") (class "Default")
      (node (ref "IC2") (pin "38") (pinfunction "(S5:3/T7:1)PB23_38") (pintype "bidirectional"))
      (node (ref "R10") (pin "1") (pinfunction "1_1") (pintype "passive"))
    )
    (net (code "30") (name "D27_~{XB2_PWR}") (class "Default")
      (node (ref "IC2") (pin "19") (pinfunction "(S4:2/T5:0|0:4)PB10_19") (pintype "bidirectional"))
      (node (ref "R20") (pin "2") (pinfunction "2_2") (pintype "passive"))
      (node (ref "T3") (pin "1") (pinfunction "G_1") (pintype "passive"))
    )
    (net (code "31") (name "D28_CS_XB2") (class "Default")
      (node (ref "IC2") (pin "23") (pinfunction "(XIN/S2:2|4:2/T3:0|0:4)PA14_23") (pintype "bidirectional"))
      (node (ref "T1") (pin "4") (pinfunction "S_4") (pintype "passive"))
    )
    (net (code "32") (name "D29_INT_XB2") (class "Default")
      (node (ref "IC2") (pin "24") (pinfunction "(XOUT/S2:3|4:3/T3:1|0:5)PA15_24") (pintype "bidirectional"))
      (node (ref "R17") (pin "2") (pinfunction "2_2") (pintype "passive"))
    )
    (net (code "33") (name "D30_TX_XB2") (class "Default")
      (node (ref "IC2") (pin "15") (pinfunction "(S0:2|2:2/T1:0|0:2/AIN18)PA10_15") (pintype "bidirectional"))
      (node (ref "R9") (pin "1") (pinfunction "1_1") (pintype "passive"))
    )
    (net (code "34") (name "D31_RX_XB2") (class "Default")
      (node (ref "IC2") (pin "16") (pinfunction "(S0:3|2:3/T1:1|0:3/AIN19)PA11_16") (pintype "bidirectional"))
      (node (ref "R11") (pin "1") (pinfunction "1_1") (pintype "passive"))
    )
    (net (code "35") (name "GND") (class "Default")
      (node (ref "C1") (pin "1") (pinfunction "1_1") (pintype "passive"))
      (node (ref "C10") (pin "1") (pinfunction "1_1") (pintype "passive"))
      (node (ref "C11") (pin "1") (pinfunction "1_1") (pintype "passive"))
      (node (ref "C12") (pin "1") (pinfunction "1_1") (pintype "passive"))
      (node (ref "C13") (pin "1") (pinfunction "1_1") (pintype "passive"))
      (node (ref "C14") (pin "2") (pinfunction "2_2") (pintype "passive"))
      (node (ref "C15") (pin "1") (pinfunction "1_1") (pintype "passive"))
      (node (ref "C16") (pin "1") (pinfunction "1_1") (pintype "passive"))
      (node (ref "C17") (pin "1") (pinfunction "1_1") (pintype "passive"))
      (node (ref "C18") (pin "1") (pinfunction "1_1") (pintype "passive"))
      (node (ref "C19") (pin "1") (pinfunction "1_1") (pintype "passive"))
      (node (ref "C2") (pin "1") (pinfunction "1_1") (pintype "passive"))
      (node (ref "C20") (pin "1") (pinfunction "1_1") (pintype "passive"))
      (node (ref "C21") (pin "1") (pinfunction "1_1") (pintype "passive"))
      (node (ref "C22") (pin "1") (pinfunction "1_1") (pintype "passive"))
      (node (ref "C23") (pin "1") (pinfunction "1_1") (pintype "passive"))
      (node (ref "C24") (pin "1") (pinfunction "1_1") (pintype "passive"))
      (node (ref "C25") (pin "1") (pinfunction "1_1") (pintype "passive"))
      (node (ref "C26") (pin "1") (pinfunction "1_1") (pintype "passive"))
      (node (ref "C27") (pin "1") (pinfunction "1_1") (pintype "passive"))
      (node (ref "C3") (pin "1") (pinfunction "1_1") (pintype "passive"))
      (node (ref "C4") (pin "1") (pinfunction "1_1") (pintype "passive"))
      (node (ref "C5") (pin "1") (pinfunction "1_1") (pintype "passive"))
      (node (ref "C6") (pin "1") (pinfunction "1_1") (pintype "passive"))
      (node (ref "C7") (pin "1") (pinfunction "1_1") (pintype "passive"))
      (node (ref "C8") (pin "1") (pinfunction "1_1") (pintype "passive"))
      (node (ref "C9") (pin "1") (pinfunction "1_1") (pintype "passive"))
      (node (ref "D10") (pin "1") (pinfunction "A_1") (pintype "passive"))
      (node (ref "D11") (pin "1") (pinfunction "A_1") (pintype "passive"))
      (node (ref "D12") (pin "1") (pinfunction "A_1") (pintype "passive"))
      (node (ref "D13") (pin "1") (pinfunction "A_1") (pintype "passive"))
      (node (ref "D14") (pin "1") (pinfunction "A_1") (pintype "passive"))
      (node (ref "D15") (pin "1") (pinfunction "A_1") (pintype "passive"))
      (node (ref "D16") (pin "C") (pinfunction "C_C") (pintype "passive"))
      (node (ref "D17") (pin "1") (pinfunction "A_1") (pintype "passive"))
      (node (ref "D18") (pin "1") (pinfunction "A_1") (pintype "passive"))
      (node (ref "D19") (pin "1") (pinfunction "A_1") (pintype "passive"))
      (node (ref "D2") (pin "C") (pinfunction "C_C") (pintype "passive"))
      (node (ref "D20") (pin "C") (pinfunction "C_C") (pintype "passive"))
      (node (ref "D3") (pin "C") (pinfunction "C_C") (pintype "passive"))
      (node (ref "D5") (pin "3") (pinfunction "A_3") (pintype "passive"))
      (node (ref "D6") (pin "A") (pinfunction "A_A") (pintype "passive"))
      (node (ref "D7") (pin "C") (pinfunction "C_C") (pintype "passive"))
      (node (ref "D8") (pin "C") (pinfunction "C_C") (pintype "passive"))
      (node (ref "D9") (pin "1") (pinfunction "A_1") (pintype "passive"))
      (node (ref "IC1") (pin "1") (pinfunction "GND_1") (pintype "power_in"))
      (node (ref "IC2") (pin "18") (pinfunction "GND_18") (pintype "power_in"))
      (node (ref "IC2") (pin "35") (pinfunction "GND_35") (pintype "power_in"))
      (node (ref "IC2") (pin "42") (pinfunction "GND_42") (pintype "power_in"))
      (node (ref "IC2") (pin "5") (pinfunction "GND_5") (pintype "power_in"))
      (node (ref "IC2") (pin "TP") (pinfunction "GND_TP") (pintype "power_in"))
      (node (ref "IC3") (pin "1") (pinfunction "GND_1") (pintype "power_in"))
      (node (ref "IC4") (pin "1") (pinfunction "GND_1") (pintype "power_in"))
      (node (ref "IC5") (pin "10") (pinfunction "GND_10") (pintype "power_in"))
      (node (ref "IC6") (pin "4") (pinfunction "GNDA_4") (pintype "power_in"))
      (node (ref "IC6") (pin "6") (pinfunction "GND_6") (pintype "power_in"))
      (node (ref "IC7") (pin "4") (pinfunction "GND_4") (pintype "power_in"))
      (node (ref "J1") (pin "GND") (pinfunction "GND_GND") (pintype "power_in"))
      (node (ref "J1") (pin "GND2") (pinfunction "GND_GND2") (pintype "power_in"))
      (node (ref "J10") (pin "1") (pinfunction "1_1") (pintype "passive"))
      (node (ref "J11") (pin "1") (pinfunction "1_1") (pintype "passive"))
      (node (ref "J12") (pin "1") (pinfunction "1_1") (pintype "passive"))
      (node (ref "J13") (pin "1") (pinfunction "1_1") (pintype "passive"))
      (node (ref "J14") (pin "1") (pinfunction "1_1") (pintype "passive"))
      (node (ref "J15") (pin "3") (pinfunction "3_3") (pintype "passive"))
      (node (ref "J2") (pin "2") (pinfunction "2_2") (pintype "passive"))
      (node (ref "J3") (pin "GND@1") (pinfunction "GND_GND@1") (pintype "power_in"))
      (node (ref "J3") (pin "GND@2") (pinfunction "GND_GND@2") (pintype "power_in"))
      (node (ref "J3") (pin "GND@3") (pinfunction "GND_GND@3") (pintype "power_in"))
      (node (ref "J4") (pin "1") (pinfunction "1_1") (pintype "passive"))
      (node (ref "J5") (pin "1") (pinfunction "1_1") (pintype "passive"))
      (node (ref "J6") (pin "1") (pinfunction "1_1") (pintype "passive"))
      (node (ref "J7") (pin "1") (pinfunction "1_1") (pintype "passive"))
      (node (ref "J8") (pin "1") (pinfunction "1_1") (pintype "passive"))
      (node (ref "J9") (pin "1") (pinfunction "1_1") (pintype "passive"))
      (node (ref "R1") (pin "1") (pinfunction "1_1") (pintype "passive"))
      (node (ref "R19") (pin "2") (pinfunction "2_2") (pintype "passive"))
      (node (ref "R21") (pin "2") (pinfunction "2_2") (pintype "passive"))
      (node (ref "R32") (pin "2") (pinfunction "2_2") (pintype "passive"))
      (node (ref "R37") (pin "2") (pinfunction "2_2") (pintype "passive"))
      (node (ref "R46") (pin "2") (pinfunction "2_2") (pintype "passive"))
      (node (ref "R47") (pin "2") (pinfunction "2_2") (pintype "passive"))
      (node (ref "SW1") (pin "3") (pinfunction "S1_3") (pintype "passive"))
      (node (ref "SW1") (pin "4") (pinfunction "S1_4") (pintype "passive"))
      (node (ref "SW2") (pin "1") (pinfunction "P1_1") (pintype "passive"))
      (node (ref "SW2") (pin "2") (pinfunction "P1_2") (pintype "passive"))
      (node (ref "T5") (pin "1") (pinfunction "S_1") (pintype "passive"))
      (node (ref "T5") (pin "4") (pinfunction "S_4") (pintype "passive"))
      (node (ref "XBEE1") (pin "10") (pinfunction "GND_10") (pintype "power_in"))
      (node (ref "XBEE2") (pin "10") (pinfunction "GND_10") (pintype "power_in"))
    )
    (net (code "36") (name "I2C_SCL") (class "Default")
      (node (ref "J10") (pin "4") (pinfunction "4_4") (pintype "passive"))
      (node (ref "J11") (pin "4") (pinfunction "4_4") (pintype "passive"))
      (node (ref "J12") (pin "4") (pinfunction "4_4") (pintype "passive"))
      (node (ref "J13") (pin "4") (pinfunction "4_4") (pintype "passive"))
      (node (ref "J9") (pin "4") (pinfunction "4_4") (pintype "passive"))
      (node (ref "R41") (pin "1") (pinfunction "1_1") (pintype "passive"))
      (node (ref "T6") (pin "6") (pinfunction "D_6") (pintype "passive"))
    )
    (net (code "37") (name "I2C_SDA") (class "Default")
      (node (ref "J10") (pin "3") (pinfunction "3_3") (pintype "passive"))
      (node (ref "J11") (pin "3") (pinfunction "3_3") (pintype "passive"))
      (node (ref "J12") (pin "3") (pinfunction "3_3") (pintype "passive"))
      (node (ref "J13") (pin "3") (pinfunction "3_3") (pintype "passive"))
      (node (ref "J9") (pin "3") (pinfunction "3_3") (pintype "passive"))
      (node (ref "R42") (pin "1") (pinfunction "1_1") (pintype "passive"))
      (node (ref "T6") (pin "3") (pinfunction "D_3") (pintype "passive"))
    )
    (net (code "38") (name "I2C_VCC") (class "Default")
      (node (ref "C24") (pin "2") (pinfunction "2_2") (pintype "passive"))
      (node (ref "J10") (pin "2") (pinfunction "2_2") (pintype "passive"))
      (node (ref "J11") (pin "2") (pinfunction "2_2") (pintype "passive"))
      (node (ref "J12") (pin "2") (pinfunction "2_2") (pintype "passive"))
      (node (ref "J13") (pin "2") (pinfunction "2_2") (pintype "passive"))
      (node (ref "J9") (pin "2") (pinfunction "2_2") (pintype "passive"))
      (node (ref "R41") (pin "2") (pinfunction "2_2") (pintype "passive"))
      (node (ref "R42") (pin "2") (pinfunction "2_2") (pintype "passive"))
      (node (ref "R43") (pin "2") (pinfunction "2_2") (pintype "passive"))
      (node (ref "T7") (pin "3") (pinfunction "D_3") (pintype "passive"))
    )
    (net (code "39") (name "IO1") (class "Default")
      (node (ref "J5") (pin "3") (pinfunction "3_3") (pintype "passive"))
      (node (ref "R31") (pin "2") (pinfunction "2_2") (pintype "passive"))
    )
    (net (code "40") (name "IO2") (class "Default")
      (node (ref "J5") (pin "4") (pinfunction "4_4") (pintype "passive"))
      (node (ref "R30") (pin "2") (pinfunction "2_2") (pintype "passive"))
    )
    (net (code "41") (name "IO3") (class "Default")
      (node (ref "J6") (pin "3") (pinfunction "3_3") (pintype "passive"))
      (node (ref "R29") (pin "2") (pinfunction "2_2") (pintype "passive"))
    )
    (net (code "42") (name "IO4") (class "Default")
      (node (ref "J6") (pin "4") (pinfunction "4_4") (pintype "passive"))
      (node (ref "R28") (pin "2") (pinfunction "2_2") (pintype "passive"))
    )
    (net (code "43") (name "IO5") (class "Default")
      (node (ref "J8") (pin "3") (pinfunction "3_3") (pintype "passive"))
      (node (ref "R27") (pin "2") (pinfunction "2_2") (pintype "passive"))
    )
    (net (code "44") (name "IO6") (class "Default")
      (node (ref "J8") (pin "4") (pinfunction "4_4") (pintype "passive"))
      (node (ref "R26") (pin "2") (pinfunction "2_2") (pintype "passive"))
    )
    (net (code "45") (name "Net-(D1-PadA)") (class "Default")
      (node (ref "D1") (pin "A") (pinfunction "A_A") (pintype "passive"))
      (node (ref "J2") (pin "1") (pinfunction "1_1") (pintype "passive"))
    )
    (net (code "46") (name "Net-(D1-PadC)") (class "Default")
      (node (ref "D1") (pin "C") (pinfunction "C_C") (pintype "passive"))
      (node (ref "F2") (pin "1") (pinfunction "1_1") (pintype "passive"))
    )
    (net (code "47") (name "Net-(D2-PadA)") (class "Default")
      (node (ref "D2") (pin "A") (pinfunction "A_A") (pintype "passive"))
      (node (ref "R3") (pin "2") (pinfunction "2_2") (pintype "passive"))
    )
    (net (code "48") (name "Net-(D3-PadA)") (class "Default")
      (node (ref "D3") (pin "A") (pinfunction "A_A") (pintype "passive"))
      (node (ref "R4") (pin "2") (pinfunction "2_2") (pintype "passive"))
    )
    (net (code "49") (name "Net-(D7-PadA)") (class "Default")
      (node (ref "D7") (pin "A") (pinfunction "A_A") (pintype "passive"))
      (node (ref "R22") (pin "1") (pinfunction "1_1") (pintype "passive"))
    )
    (net (code "50") (name "Net-(D8-PadA)") (class "Default")
      (node (ref "D8") (pin "A") (pinfunction "A_A") (pintype "passive"))
      (node (ref "R23") (pin "1") (pinfunction "1_1") (pintype "passive"))
    )
    (net (code "51") (name "Net-(D16-PadA)") (class "Default")
      (node (ref "D16") (pin "A") (pinfunction "A_A") (pintype "passive"))
      (node (ref "R34") (pin "1") (pinfunction "1_1") (pintype "passive"))
    )
    (net (code "52") (name "Net-(D20-PadA)") (class "Default")
      (node (ref "D20") (pin "A") (pinfunction "A_A") (pintype "passive"))
      (node (ref "R43") (pin "1") (pinfunction "1_1") (pintype "passive"))
    )
    (net (code "53") (name "Net-(F1-Pad1)") (class "Default")
      (node (ref "F1") (pin "1") (pinfunction "1_1") (pintype "passive"))
      (node (ref "J1") (pin "VBUS") (pinfunction "VBUS_VBUS") (pintype "power_in"))
      (node (ref "J1") (pin "VBUS2") (pinfunction "VBUS_VBUS2") (pintype "power_in"))
    )
    (net (code "54") (name "Net-(IC2-(XIN32{slash}S1:0{slash}T2:0)PA00)") (class "Default")
      (node (ref "C14") (pin "1") (pinfunction "1_1") (pintype "passive"))
      (node (ref "IC2") (pin "1") (pinfunction "(XIN32/S1:0/T2:0)PA00_1") (pintype "bidirectional"))
      (node (ref "Q1") (pin "2") (pinfunction "2_2") (pintype "passive"))
    )
    (net (code "55") (name "Net-(IC2-(XOUT32{slash}S1:1{slash}T2:1)PA01)") (class "Default")
      (node (ref "C15") (pin "2") (pinfunction "2_2") (pintype "passive"))
      (node (ref "IC2") (pin "2") (pinfunction "(XOUT32/S1:1/T2:1)PA01_2") (pintype "bidirectional"))
      (node (ref "Q1") (pin "1") (pinfunction "1_1") (pintype "passive"))
    )
    (net (code "56") (name "Net-(IC2-VCCANA)") (class "Default")
      (node (ref "C10") (pin "2") (pinfunction "2_2") (pintype "passive"))
      (node (ref "C11") (pin "2") (pinfunction "2_2") (pintype "passive"))
      (node (ref "C8") (pin "2") (pinfunction "2_2") (pintype "passive"))
      (node (ref "IC2") (pin "6") (pinfunction "VCCANA_6") (pintype "power_in"))
      (node (ref "L1") (pin "2") (pinfunction "2_2") (pintype "passive"))
    )
    (net (code "57") (name "Net-(IC2-VCCCORE)") (class "Default")
      (node (ref "C13") (pin "2") (pinfunction "2_2") (pintype "passive"))
      (node (ref "IC2") (pin "43") (pinfunction "VCCCORE_43") (pintype "power_in"))
    )
    (net (code "58") (name "Net-(IC3-RST)") (class "Default")
      (node (ref "IC3") (pin "2") (pinfunction "RST_2") (pintype "output"))
      (node (ref "XBEE2") (pin "5") (pinfunction "~{RESET}_5") (pintype "bidirectional"))
    )
    (net (code "59") (name "Net-(IC4-RST)") (class "Default")
      (node (ref "IC4") (pin "2") (pinfunction "RST_2") (pintype "output"))
      (node (ref "XBEE1") (pin "5") (pinfunction "~{RESET}_5") (pintype "bidirectional"))
    )
    (net (code "60") (name "Net-(IC5A-A1)") (class "Default")
      (node (ref "IC5") (pin "1") (pinfunction "G_1") (pintype "input"))
      (node (ref "IC5") (pin "2") (pinfunction "A1_2") (pintype "input"))
      (node (ref "R12") (pin "1") (pinfunction "1_1") (pintype "passive"))
      (node (ref "T1") (pin "6") (pinfunction "D_6") (pintype "passive"))
    )
    (net (code "61") (name "Net-(IC5B-A4)") (class "Default")
      (node (ref "IC5") (pin "17") (pinfunction "A4_17") (pintype "input"))
      (node (ref "IC5") (pin "19") (pinfunction "G_19") (pintype "input"))
      (node (ref "R13") (pin "1") (pinfunction "1_1") (pintype "passive"))
      (node (ref "T1") (pin "3") (pinfunction "D_3") (pintype "passive"))
    )
    (net (code "62") (name "Net-(IC6-SDO1)") (class "Default")
      (node (ref "IC6") (pin "17") (pinfunction "SDO1_17") (pintype "bidirectional"))
      (node (ref "J15") (pin "2") (pinfunction "2_2") (pintype "passive"))
    )
    (net (code "63") (name "Net-(IC6-SDO2)") (class "Default")
      (node (ref "IC6") (pin "12") (pinfunction "SDO2_12") (pintype "bidirectional"))
      (node (ref "J14") (pin "2") (pinfunction "2_2") (pintype "passive"))
    )
    (net (code "64") (name "Net-(J1-CC1)") (class "Default")
      (node (ref "J1") (pin "A5") (pinfunction "CC1_A5") (pintype "bidirectional"))
      (node (ref "R46") (pin "1") (pinfunction "1_1") (pintype "passive"))
    )
    (net (code "65") (name "Net-(J1-CC2)") (class "Default")
      (node (ref "J1") (pin "B5") (pinfunction "CC2_B5") (pintype "bidirectional"))
      (node (ref "R47") (pin "1") (pinfunction "1_1") (pintype "passive"))
    )
    (net (code "66") (name "Net-(J1-SHIELD-PadS@1)") (class "Default")
      (node (ref "J1") (pin "S@1") (pinfunction "SHIELD_S@1") (pintype "passive"))
      (node (ref "J1") (pin "S@2") (pinfunction "SHIELD_S@2") (pintype "passive"))
      (node (ref "J1") (pin "S@3") (pinfunction "SHIELD_S@3") (pintype "passive"))
      (node (ref "J1") (pin "S@4") (pinfunction "SHIELD_S@4") (pintype "passive"))
      (node (ref "J1") (pin "S@5") (pinfunction "SHIELD_S@5") (pintype "passive"))
      (node (ref "J1") (pin "S@6") (pinfunction "SHIELD_S@6") (pintype "passive"))
      (node (ref "J1") (pin "S@7") (pinfunction "SHIELD_S@7") (pintype "passive"))
      (node (ref "J1") (pin "S@8") (pinfunction "SHIELD_S@8") (pintype "passive"))
      (node (ref "J1") (pin "S@9") (pinfunction "SHIELD_S@9") (pintype "passive"))
      (node (ref "R1") (pin "2") (pinfunction "2_2") (pintype "passive"))
    )
    (net (code "67") (name "Net-(J4-Pad3)") (class "Default")
      (node (ref "J4") (pin "3") (pinfunction "3_3") (pintype "passive"))
      (node (ref "R25") (pin "2") (pinfunction "2_2") (pintype "passive"))
    )
    (net (code "68") (name "Net-(J4-Pad4)") (class "Default")
      (node (ref "J4") (pin "4") (pinfunction "4_4") (pintype "passive"))
      (node (ref "R24") (pin "2") (pinfunction "2_2") (pintype "passive"))
    )
    (net (code "69") (name "Net-(J7-Pad3)") (class "Default")
      (node (ref "J7") (pin "3") (pinfunction "3_3") (pintype "passive"))
      (node (ref "R36") (pin "2") (pinfunction "2_2") (pintype "passive"))
    )
    (net (code "70") (name "Net-(J7-Pad4)") (class "Default")
      (node (ref "J7") (pin "4") (pinfunction "4_4") (pintype "passive"))
      (node (ref "R35") (pin "2") (pinfunction "2_2") (pintype "passive"))
    )
    (net (code "71") (name "Net-(R2-Pad2)") (class "Default")
      (node (ref "R2") (pin "2") (pinfunction "2_2") (pintype "passive"))
      (node (ref "SW1") (pin "1") (pinfunction "P1_1") (pintype "passive"))
      (node (ref "SW1") (pin "2") (pinfunction "P1_2") (pintype "passive"))
    )
    (net (code "72") (name "Net-(R6-Pad2)") (class "Default")
      (node (ref "R6") (pin "2") (pinfunction "2_2") (pintype "passive"))
      (node (ref "SW2") (pin "3") (pinfunction "S1_3") (pintype "passive"))
      (node (ref "SW2") (pin "4") (pinfunction "S1_4") (pintype "passive"))
    )
    (net (code "73") (name "Net-(T4-G)") (class "Default")
      (node (ref "R33") (pin "2") (pinfunction "2_2") (pintype "passive"))
      (node (ref "T4") (pin "1") (pinfunction "G_1") (pintype "passive"))
      (node (ref "T5") (pin "3") (pinfunction "D_3") (pintype "passive"))
    )
    (net (code "74") (name "Net-(T5A-D)") (class "Default")
      (node (ref "R40") (pin "2") (pinfunction "2_2") (pintype "passive"))
      (node (ref "T5") (pin "6") (pinfunction "D_6") (pintype "passive"))
      (node (ref "T7") (pin "1") (pinfunction "G_1") (pintype "passive"))
    )
    (net (code "75") (name "Net-(XBEE1-DIN{slash}RX{slash}~{CFG})") (class "Default")
      (node (ref "R8") (pin "2") (pinfunction "2_2") (pintype "passive"))
      (node (ref "XBEE1") (pin "3") (pinfunction "DIN/RX/~{CFG}_3") (pintype "bidirectional"))
    )
    (net (code "76") (name "Net-(XBEE1-DIO7{slash}CTS)") (class "Default")
      (node (ref "R15") (pin "1") (pinfunction "1_1") (pintype "passive"))
      (node (ref "XBEE1") (pin "12") (pinfunction "DIO7/CTS_12") (pintype "bidirectional"))
    )
    (net (code "77") (name "Net-(XBEE1-DOUT{slash}TX)") (class "Default")
      (node (ref "R10") (pin "2") (pinfunction "2_2") (pintype "passive"))
      (node (ref "XBEE1") (pin "2") (pinfunction "DOUT/TX_2") (pintype "bidirectional"))
    )
    (net (code "78") (name "Net-(XBEE2-DIN{slash}RX{slash}~{CFG})") (class "Default")
      (node (ref "R9") (pin "2") (pinfunction "2_2") (pintype "passive"))
      (node (ref "XBEE2") (pin "3") (pinfunction "DIN/RX/~{CFG}_3") (pintype "bidirectional"))
    )
    (net (code "79") (name "Net-(XBEE2-DIO7{slash}CTS)") (class "Default")
      (node (ref "R17") (pin "1") (pinfunction "1_1") (pintype "passive"))
      (node (ref "XBEE2") (pin "12") (pinfunction "DIO7/CTS_12") (pintype "bidirectional"))
    )
    (net (code "80") (name "Net-(XBEE2-DOUT{slash}TX)") (class "Default")
      (node (ref "R11") (pin "2") (pinfunction "2_2") (pintype "passive"))
      (node (ref "XBEE2") (pin "2") (pinfunction "DOUT/TX_2") (pintype "bidirectional"))
    )
    (net (code "81") (name "RST") (class "Default")
      (node (ref "C12") (pin "2") (pinfunction "2_2") (pintype "passive"))
      (node (ref "IC2") (pin "40") (pinfunction "~{RESET}_40") (pintype "input"))
      (node (ref "J3") (pin "RST") (pinfunction "RST_RST") (pintype "bidirectional"))
      (node (ref "R6") (pin "1") (pinfunction "1_1") (pintype "passive"))
      (node (ref "R7") (pin "2") (pinfunction "2_2") (pintype "passive"))
    )
    (net (code "82") (name "SWCLK") (class "Default")
      (node (ref "IC2") (pin "45") (pinfunction "(SWCLK/S1:2/T1:0)PA30_45") (pintype "bidirectional"))
      (node (ref "J3") (pin "SWCLK") (pinfunction "SWCLK_SWCLK") (pintype "bidirectional"))
      (node (ref "R5") (pin "2") (pinfunction "2_2") (pintype "passive"))
    )
    (net (code "83") (name "SWDIO") (class "Default")
      (node (ref "IC2") (pin "46") (pinfunction "(SWDIO/S1:3/T1:1)PA31_46") (pintype "bidirectional"))
      (node (ref "J3") (pin "SWDIO") (pinfunction "SWDIO_SWDIO") (pintype "bidirectional"))
    )
    (net (code "84") (name "UART_VCC") (class "Default")
      (node (ref "C23") (pin "2") (pinfunction "2_2") (pintype "passive"))
      (node (ref "J4") (pin "2") (pinfunction "2_2") (pintype "passive"))
      (node (ref "J7") (pin "2") (pinfunction "2_2") (pintype "passive"))
      (node (ref "R34") (pin "2") (pinfunction "2_2") (pintype "passive"))
      (node (ref "T4") (pin "3") (pinfunction "D_3") (pintype "passive"))
    )
    (net (code "85") (name "USB_D_N") (class "Default")
      (node (ref "D5") (pin "1") (pinfunction "C1_1") (pintype "passive"))
      (node (ref "IC2") (pin "33") (pinfunction "(USBM/S3:2|5:2/T5:0|1:2)PA24_33") (pintype "bidirectional"))
      (node (ref "J1") (pin "A7") (pinfunction "D-_A7") (pintype "bidirectional"))
      (node (ref "J1") (pin "B7") (pinfunction "D-_B7") (pintype "bidirectional"))
    )
    (net (code "86") (name "USB_D_P") (class "Default")
      (node (ref "D5") (pin "2") (pinfunction "C2_2") (pintype "passive"))
      (node (ref "IC2") (pin "34") (pinfunction "(USBP/S3:3|5:3/T5:1|1:3)PA25_34") (pintype "bidirectional"))
      (node (ref "J1") (pin "A6") (pinfunction "D+_A6") (pintype "bidirectional"))
      (node (ref "J1") (pin "B6") (pinfunction "D+_B6") (pintype "bidirectional"))
    )
    (net (code "87") (name "XB1_CS") (class "Default")
      (node (ref "IC5") (pin "18") (pinfunction "Y1_18") (pintype "tri_state"))
      (node (ref "R14") (pin "1") (pinfunction "1_1") (pintype "passive"))
      (node (ref "XBEE1") (pin "17") (pinfunction "AD3/DIO3/SS_17") (pintype "bidirectional"))
    )
    (net (code "88") (name "XB1_MISO") (class "Default")
      (node (ref "IC5") (pin "8") (pinfunction "A4_8") (pintype "input"))
      (node (ref "XBEE1") (pin "4") (pinfunction "MISO/DIO12_4") (pintype "bidirectional"))
    )
    (net (code "89") (name "XB1_MOSI") (class "Default")
      (node (ref "IC5") (pin "16") (pinfunction "Y2_16") (pintype "tri_state"))
      (node (ref "XBEE1") (pin "11") (pinfunction "DIO4/MOSI_11") (pintype "bidirectional"))
    )
    (net (code "90") (name "XB1_SCK") (class "Default")
      (node (ref "IC5") (pin "14") (pinfunction "Y3_14") (pintype "tri_state"))
      (node (ref "XBEE1") (pin "18") (pinfunction "AD2/DIO2/SCK_18") (pintype "bidirectional"))
    )
    (net (code "91") (name "XB1_VCC") (class "Default")
      (node (ref "C16") (pin "2") (pinfunction "2_2") (pintype "passive"))
      (node (ref "C18") (pin "2") (pinfunction "2_2") (pintype "passive"))
      (node (ref "C20") (pin "2") (pinfunction "2_2") (pintype "passive"))
      (node (ref "IC4") (pin "3") (pinfunction "VCC_3") (pintype "power_in"))
      (node (ref "R14") (pin "2") (pinfunction "2_2") (pintype "passive"))
      (node (ref "R19") (pin "1") (pinfunction "1_1") (pintype "passive"))
      (node (ref "R22") (pin "2") (pinfunction "2_2") (pintype "passive"))
      (node (ref "T1") (pin "2") (pinfunction "G_2") (pintype "passive"))
      (node (ref "T2") (pin "3") (pinfunction "D_3") (pintype "passive"))
      (node (ref "XBEE1") (pin "1") (pinfunction "VCC_1") (pintype "power_in"))
    )
    (net (code "92") (name "XB2_CS") (class "Default")
      (node (ref "IC5") (pin "3") (pinfunction "Y4_3") (pintype "tri_state"))
      (node (ref "R16") (pin "1") (pinfunction "1_1") (pintype "passive"))
      (node (ref "XBEE2") (pin "17") (pinfunction "AD3/DIO3/SS_17") (pintype "bidirectional"))
    )
    (net (code "93") (name "XB2_MISO") (class "Default")
      (node (ref "IC5") (pin "11") (pinfunction "A1_11") (pintype "input"))
      (node (ref "XBEE2") (pin "4") (pinfunction "MISO/DIO12_4") (pintype "bidirectional"))
    )
    (net (code "94") (name "XB2_MOSI") (class "Default")
      (node (ref "IC5") (pin "7") (pinfunction "Y2_7") (pintype "tri_state"))
      (node (ref "XBEE2") (pin "11") (pinfunction "DIO4/MOSI_11") (pintype "bidirectional"))
    )
    (net (code "95") (name "XB2_SCK") (class "Default")
      (node (ref "IC5") (pin "5") (pinfunction "Y3_5") (pintype "tri_state"))
      (node (ref "XBEE2") (pin "18") (pinfunction "AD2/DIO2/SCK_18") (pintype "bidirectional"))
    )
    (net (code "96") (name "XB2_VCC") (class "Default")
      (node (ref "C17") (pin "2") (pinfunction "2_2") (pintype "passive"))
      (node (ref "C19") (pin "2") (pinfunction "2_2") (pintype "passive"))
      (node (ref "C21") (pin "2") (pinfunction "2_2") (pintype "passive"))
      (node (ref "IC3") (pin "3") (pinfunction "VCC_3") (pintype "power_in"))
      (node (ref "R16") (pin "2") (pinfunction "2_2") (pintype "passive"))
      (node (ref "R21") (pin "1") (pinfunction "1_1") (pintype "passive"))
      (node (ref "R23") (pin "2") (pinfunction "2_2") (pintype "passive"))
      (node (ref "T1") (pin "5") (pinfunction "G_5") (pintype "passive"))
      (node (ref "T3") (pin "3") (pinfunction "D_3") (pintype "passive"))
      (node (ref "XBEE2") (pin "1") (pinfunction "VCC_1") (pintype "power_in"))
    )
    (net (code "97") (name "unconnected-(IC6-CSB1-Pad16)") (class "Default")
      (node (ref "IC6") (pin "16") (pinfunction "CSB1_16") (pintype "bidirectional"))
    )
    (net (code "98") (name "unconnected-(IC6-CSB2-Pad5)") (class "Default")
      (node (ref "IC6") (pin "5") (pinfunction "CSB2_5") (pintype "bidirectional"))
    )
    (net (code "99") (name "unconnected-(IC6-CSB3-Pad20)") (class "Default")
      (node (ref "IC6") (pin "20") (pinfunction "CSB3_20") (pintype "bidirectional"))
    )
    (net (code "100") (name "unconnected-(IC6-DRDYM-Pad2)") (class "Default")
      (node (ref "IC6") (pin "2") (pinfunction "DRDYM_2") (pintype "bidirectional"))
    )
    (net (code "101") (name "unconnected-(IC6-INT1-Pad19)") (class "Default")
      (node (ref "IC6") (pin "19") (pinfunction "INT1_19") (pintype "output"))
    )
    (net (code "102") (name "unconnected-(IC6-INT2-Pad1)") (class "Default")
      (node (ref "IC6") (pin "1") (pinfunction "INT2_1") (pintype "output"))
    )
    (net (code "103") (name "unconnected-(IC6-INT3-Pad14)") (class "Default")
      (node (ref "IC6") (pin "14") (pinfunction "INT3_14") (pintype "output"))
    )
    (net (code "104") (name "unconnected-(IC6-INT4-Pad15)") (class "Default")
      (node (ref "IC6") (pin "15") (pinfunction "INT4_15") (pintype "output"))
    )
    (net (code "105") (name "unconnected-(IC6-INT5-Pad10)") (class "Default")
      (node (ref "IC6") (pin "10") (pinfunction "INT5_10") (pintype "bidirectional"))
    )
    (net (code "106") (name "unconnected-(XBEE1-AD0{slash}DIO0{slash}SDA{slash}CB-Pad20)") (class "Default")
      (node (ref "XBEE1") (pin "20") (pinfunction "AD0/DIO0/SDA/CB_20") (pintype "bidirectional"))
    )
    (net (code "107") (name "unconnected-(XBEE1-AD1{slash}DIO1{slash}SCL{slash}ATTN-Pad19)") (class "Default")
      (node (ref "XBEE1") (pin "19") (pinfunction "AD1/DIO1/SCL/ATTN_19") (pintype "bidirectional"))
    )
    (net (code "108") (name "unconnected-(XBEE1-DIO5{slash}ASSC-Pad15)") (class "Default")
      (node (ref "XBEE1") (pin "15") (pinfunction "DIO5/ASSC_15") (pintype "bidirectional"))
    )
    (net (code "109") (name "unconnected-(XBEE1-DIO6{slash}RTS-Pad16)") (class "Default")
      (node (ref "XBEE1") (pin "16") (pinfunction "DIO6/RTS_16") (pintype "bidirectional"))
    )
    (net (code "110") (name "unconnected-(XBEE1-DIO9{slash}ON_~{SLEEP}-Pad13)") (class "Default")
      (node (ref "XBEE1") (pin "13") (pinfunction "DIO9/ON_~{SLEEP}_13") (pintype "bidirectional"))
    )
    (net (code "111") (name "unconnected-(XBEE1-DTR{slash}DIO8-Pad9)") (class "Default")
      (node (ref "XBEE1") (pin "9") (pinfunction "DTR/DIO8_9") (pintype "bidirectional"))
    )
    (net (code "112") (name "unconnected-(XBEE1-PWM1{slash}DIO11-Pad7)") (class "Default")
      (node (ref "XBEE1") (pin "7") (pinfunction "PWM1/DIO11_7") (pintype "bidirectional"))
    )
    (net (code "113") (name "unconnected-(XBEE1-RES-Pad8)") (class "Default")
      (node (ref "XBEE1") (pin "8") (pinfunction "RES_8") (pintype "bidirectional"))
    )
    (net (code "114") (name "unconnected-(XBEE1-RSSI{slash}PWM0{slash}DIO10-Pad6)") (class "Default")
      (node (ref "XBEE1") (pin "6") (pinfunction "RSSI/PWM0/DIO10_6") (pintype "bidirectional"))
    )
    (net (code "115") (name "unconnected-(XBEE1-VREF-Pad14)") (class "Default")
      (node (ref "XBEE1") (pin "14") (pinfunction "VREF_14") (pintype "bidirectional"))
    )
    (net (code "116") (name "unconnected-(XBEE2-AD0{slash}DIO0{slash}SDA{slash}CB-Pad20)") (class "Default")
      (node (ref "XBEE2") (pin "20") (pinfunction "AD0/DIO0/SDA/CB_20") (pintype "bidirectional"))
    )
    (net (code "117") (name "unconnected-(XBEE2-AD1{slash}DIO1{slash}SCL{slash}ATTN-Pad19)") (class "Default")
      (node (ref "XBEE2") (pin "19") (pinfunction "AD1/DIO1/SCL/ATTN_19") (pintype "bidirectional"))
    )
    (net (code "118") (name "unconnected-(XBEE2-DIO5{slash}ASSC-Pad15)") (class "Default")
      (node (ref "XBEE2") (pin "15") (pinfunction "DIO5/ASSC_15") (pintype "bidirectional"))
    )
    (net (code "119") (name "unconnected-(XBEE2-DIO6{slash}RTS-Pad16)") (class "Default")
      (node (ref "XBEE2") (pin "16") (pinfunction "DIO6/RTS_16") (pintype "bidirectional"))
    )
    (net (code "120") (name "unconnected-(XBEE2-DIO9{slash}ON_~{SLEEP}-Pad13)") (class "Default")
      (node (ref "XBEE2") (pin "13") (pinfunction "DIO9/ON_~{SLEEP}_13") (pintype "bidirectional"))
    )
    (net (code "121") (name "unconnected-(XBEE2-DTR{slash}DIO8-Pad9)") (class "Default")
      (node (ref "XBEE2") (pin "9") (pinfunction "DTR/DIO8_9") (pintype "bidirectional"))
    )
    (net (code "122") (name "unconnected-(XBEE2-PWM1{slash}DIO11-Pad7)") (class "Default")
      (node (ref "XBEE2") (pin "7") (pinfunction "PWM1/DIO11_7") (pintype "bidirectional"))
    )
    (net (code "123") (name "unconnected-(XBEE2-RES-Pad8)") (class "Default")
      (node (ref "XBEE2") (pin "8") (pinfunction "RES_8") (pintype "bidirectional"))
    )
    (net (code "124") (name "unconnected-(XBEE2-RSSI{slash}PWM0{slash}DIO10-Pad6)") (class "Default")
      (node (ref "XBEE2") (pin "6") (pinfunction "RSSI/PWM0/DIO10_6") (pintype "bidirectional"))
    )
    (net (code "125") (name "unconnected-(XBEE2-VREF-Pad14)") (class "Default")
      (node (ref "XBEE2") (pin "14") (pinfunction "VREF_14") (pintype "bidirectional"))
    )
  )
)
